# VDA_spanish.net
KiCad netlist of a schematic drawn in EAGLE
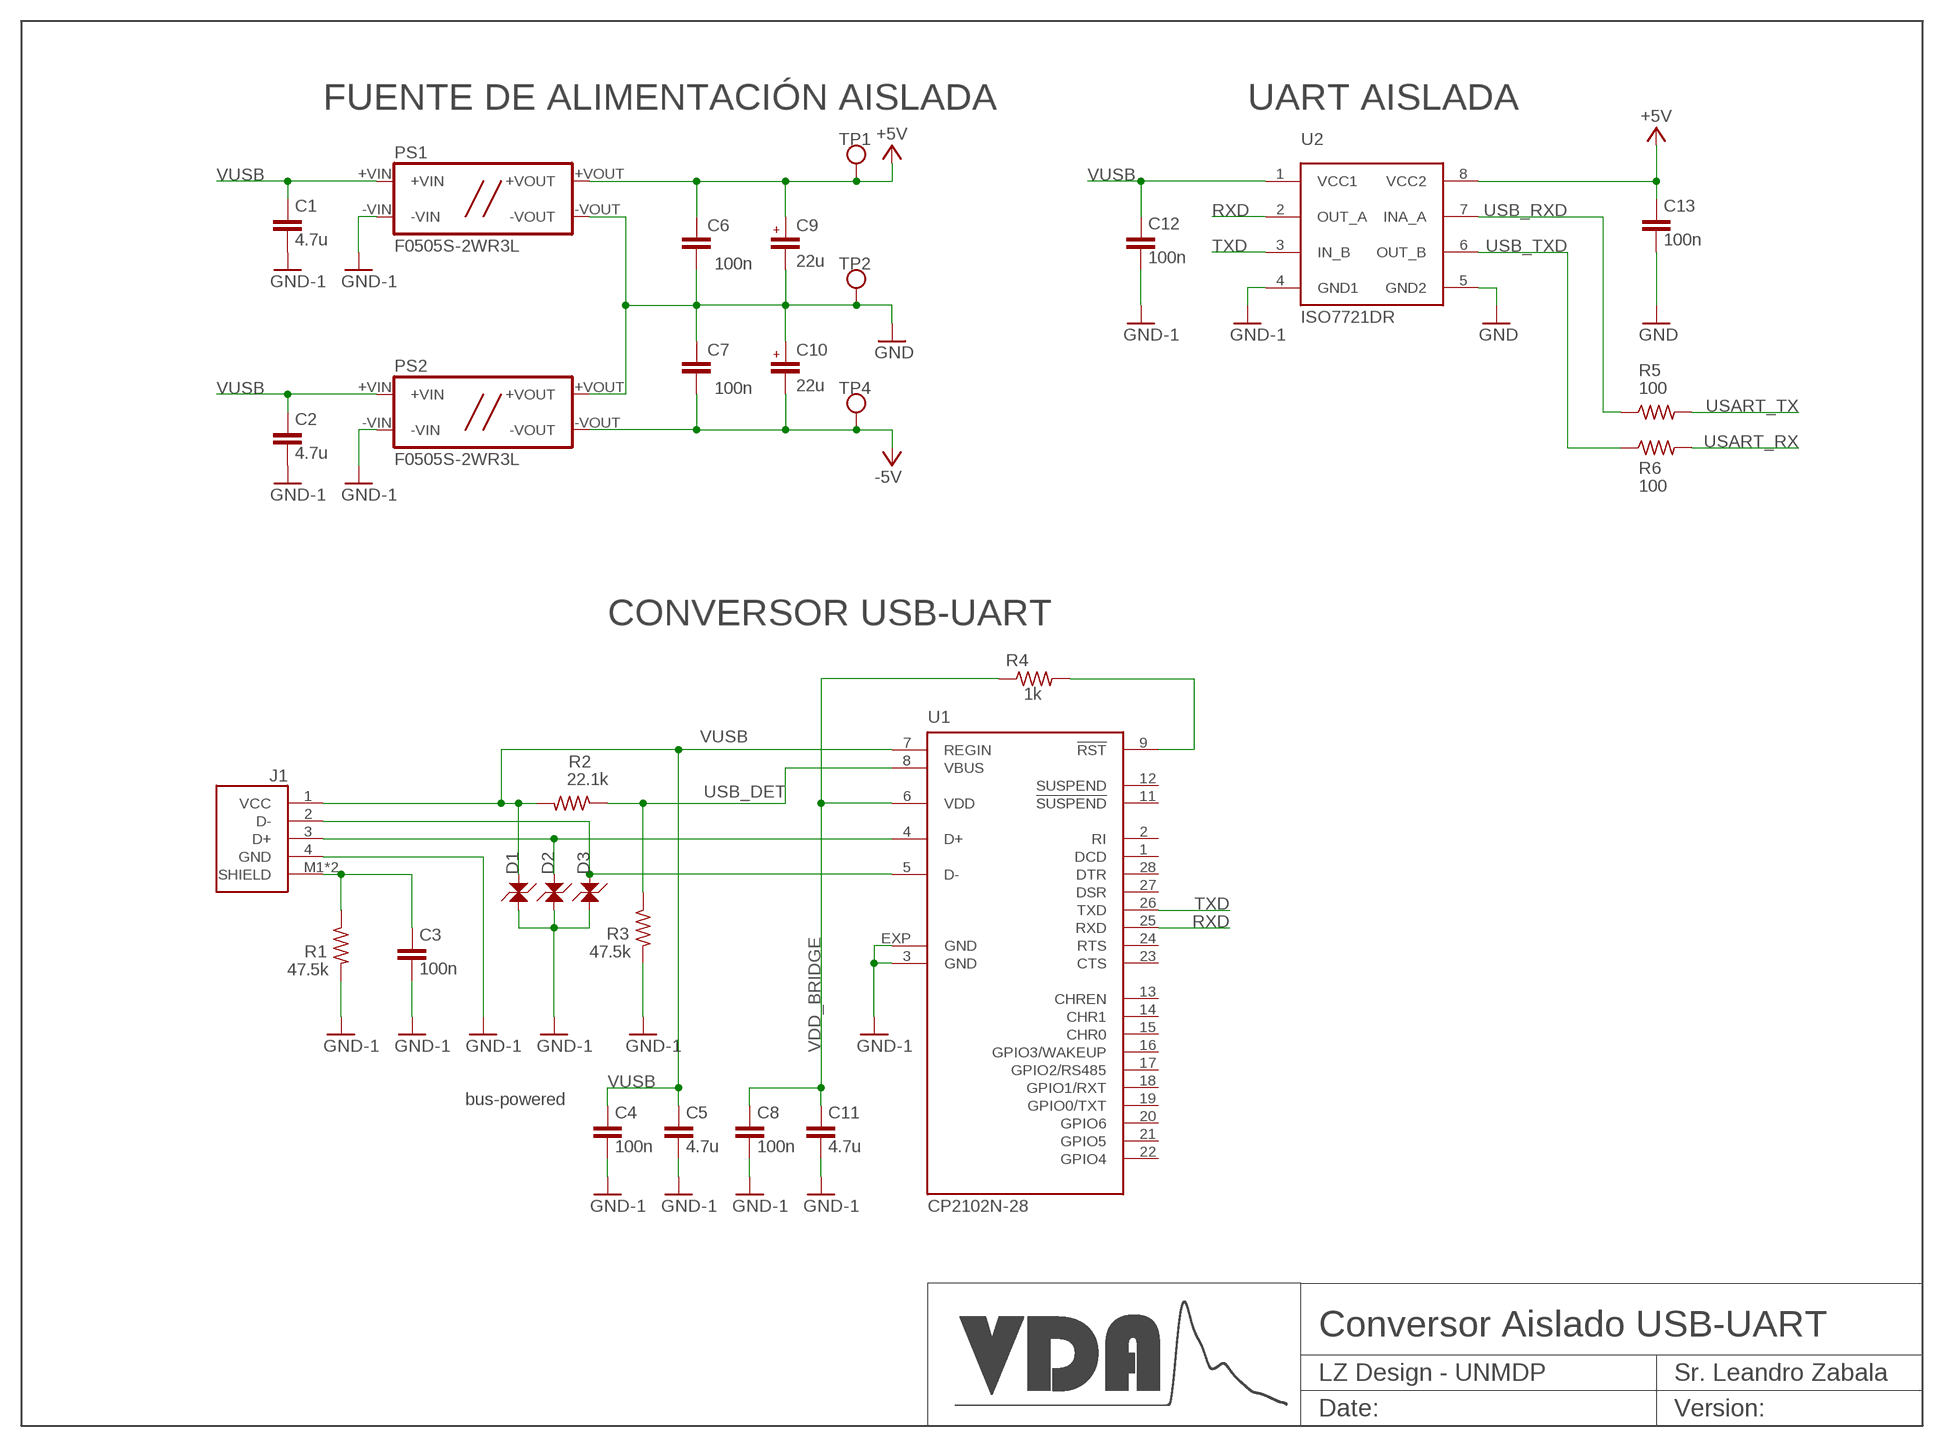
[diagram p0: schematic, sheet 1]
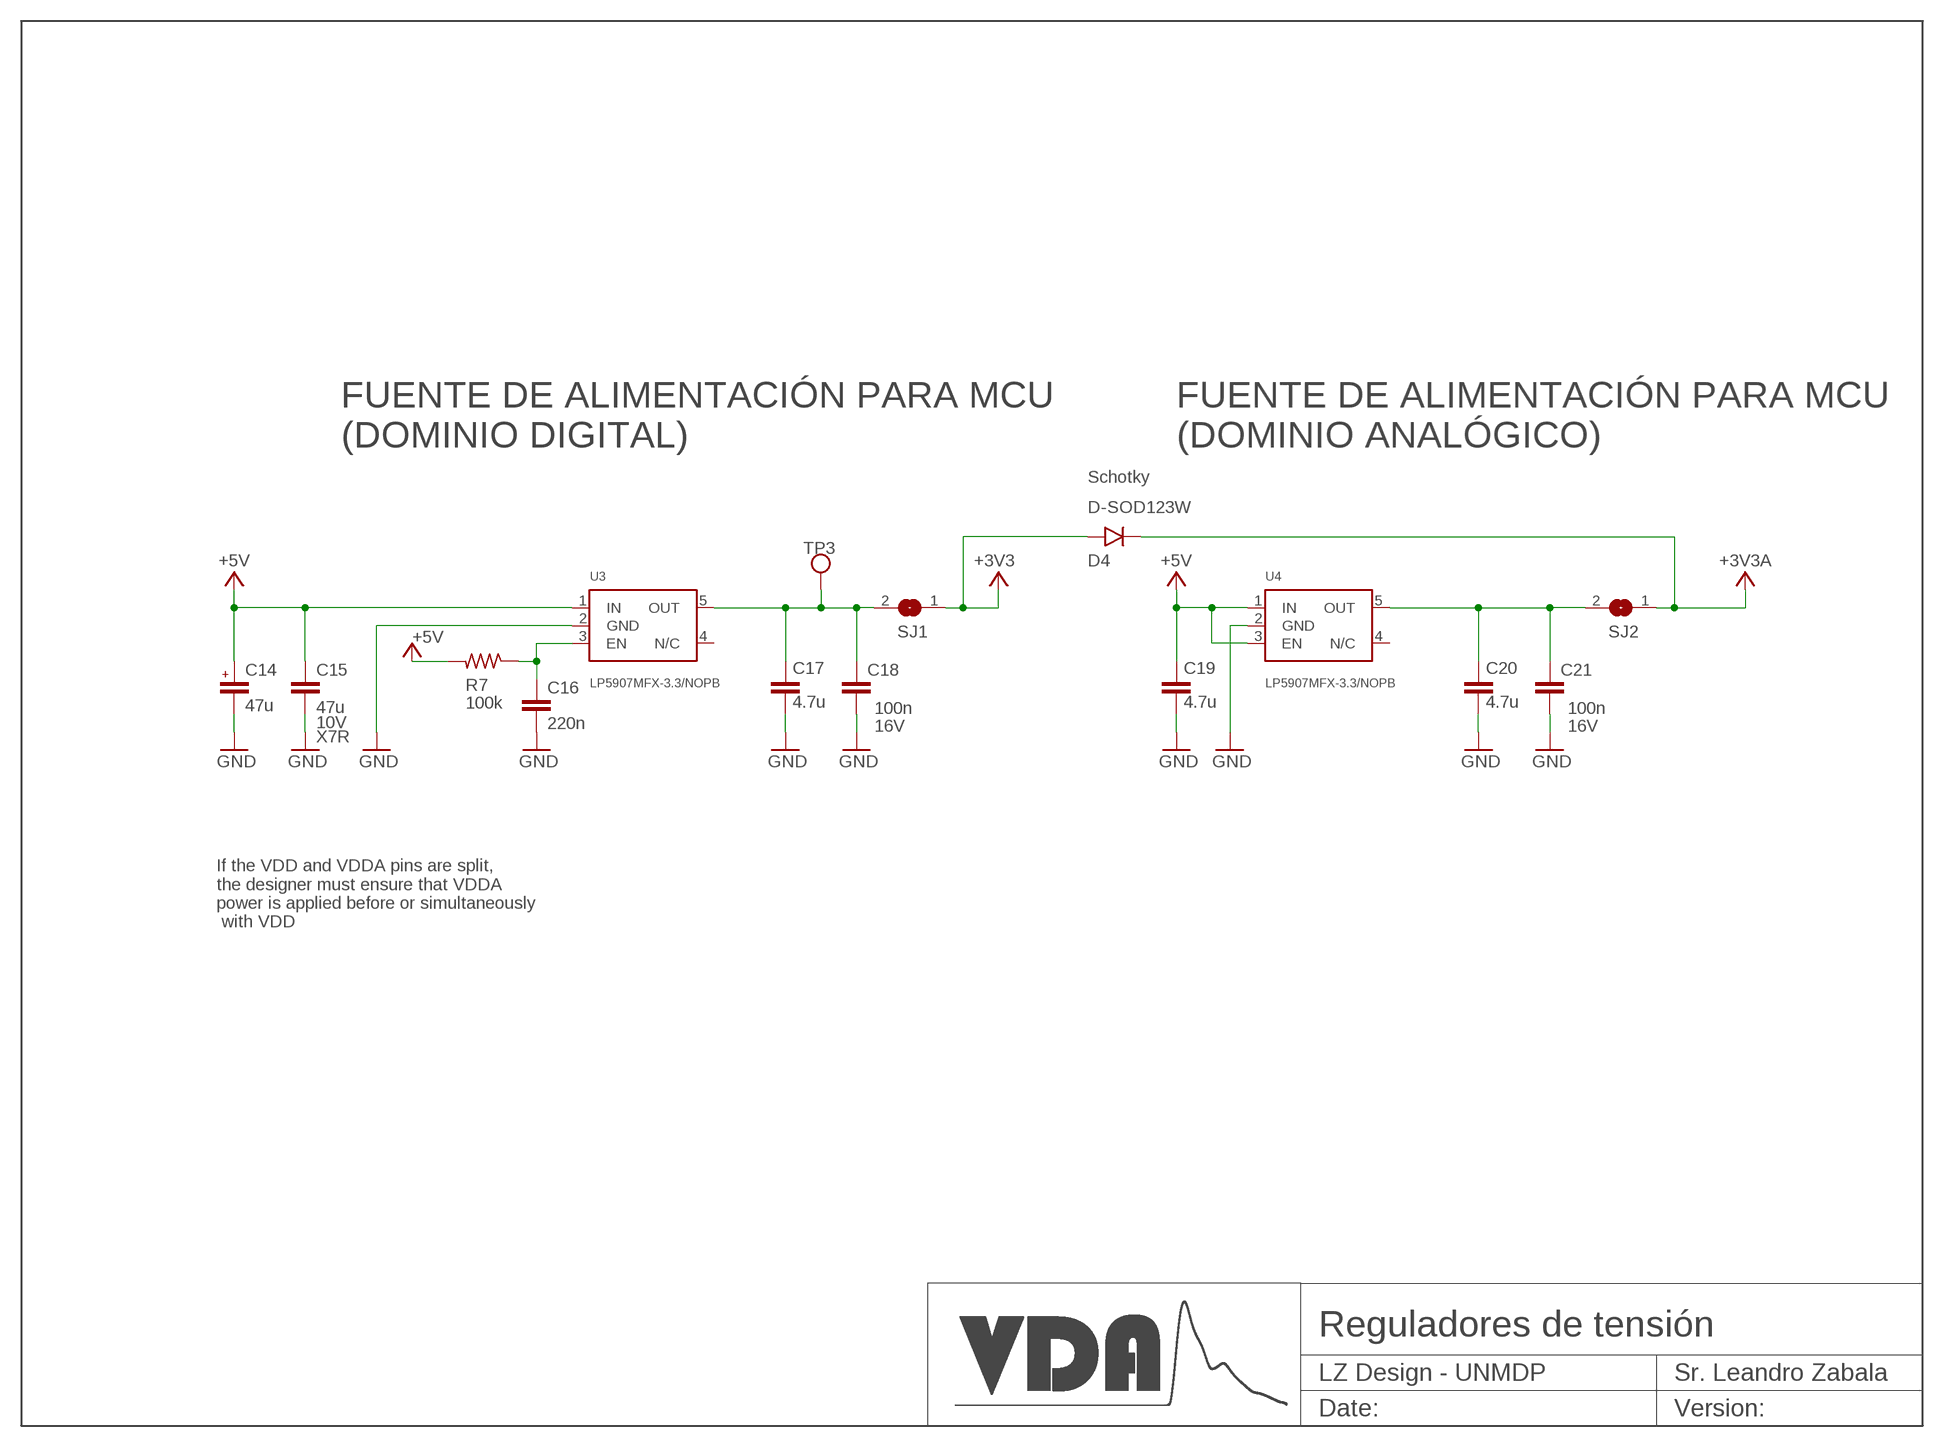
[diagram p1: schematic, sheet 2]
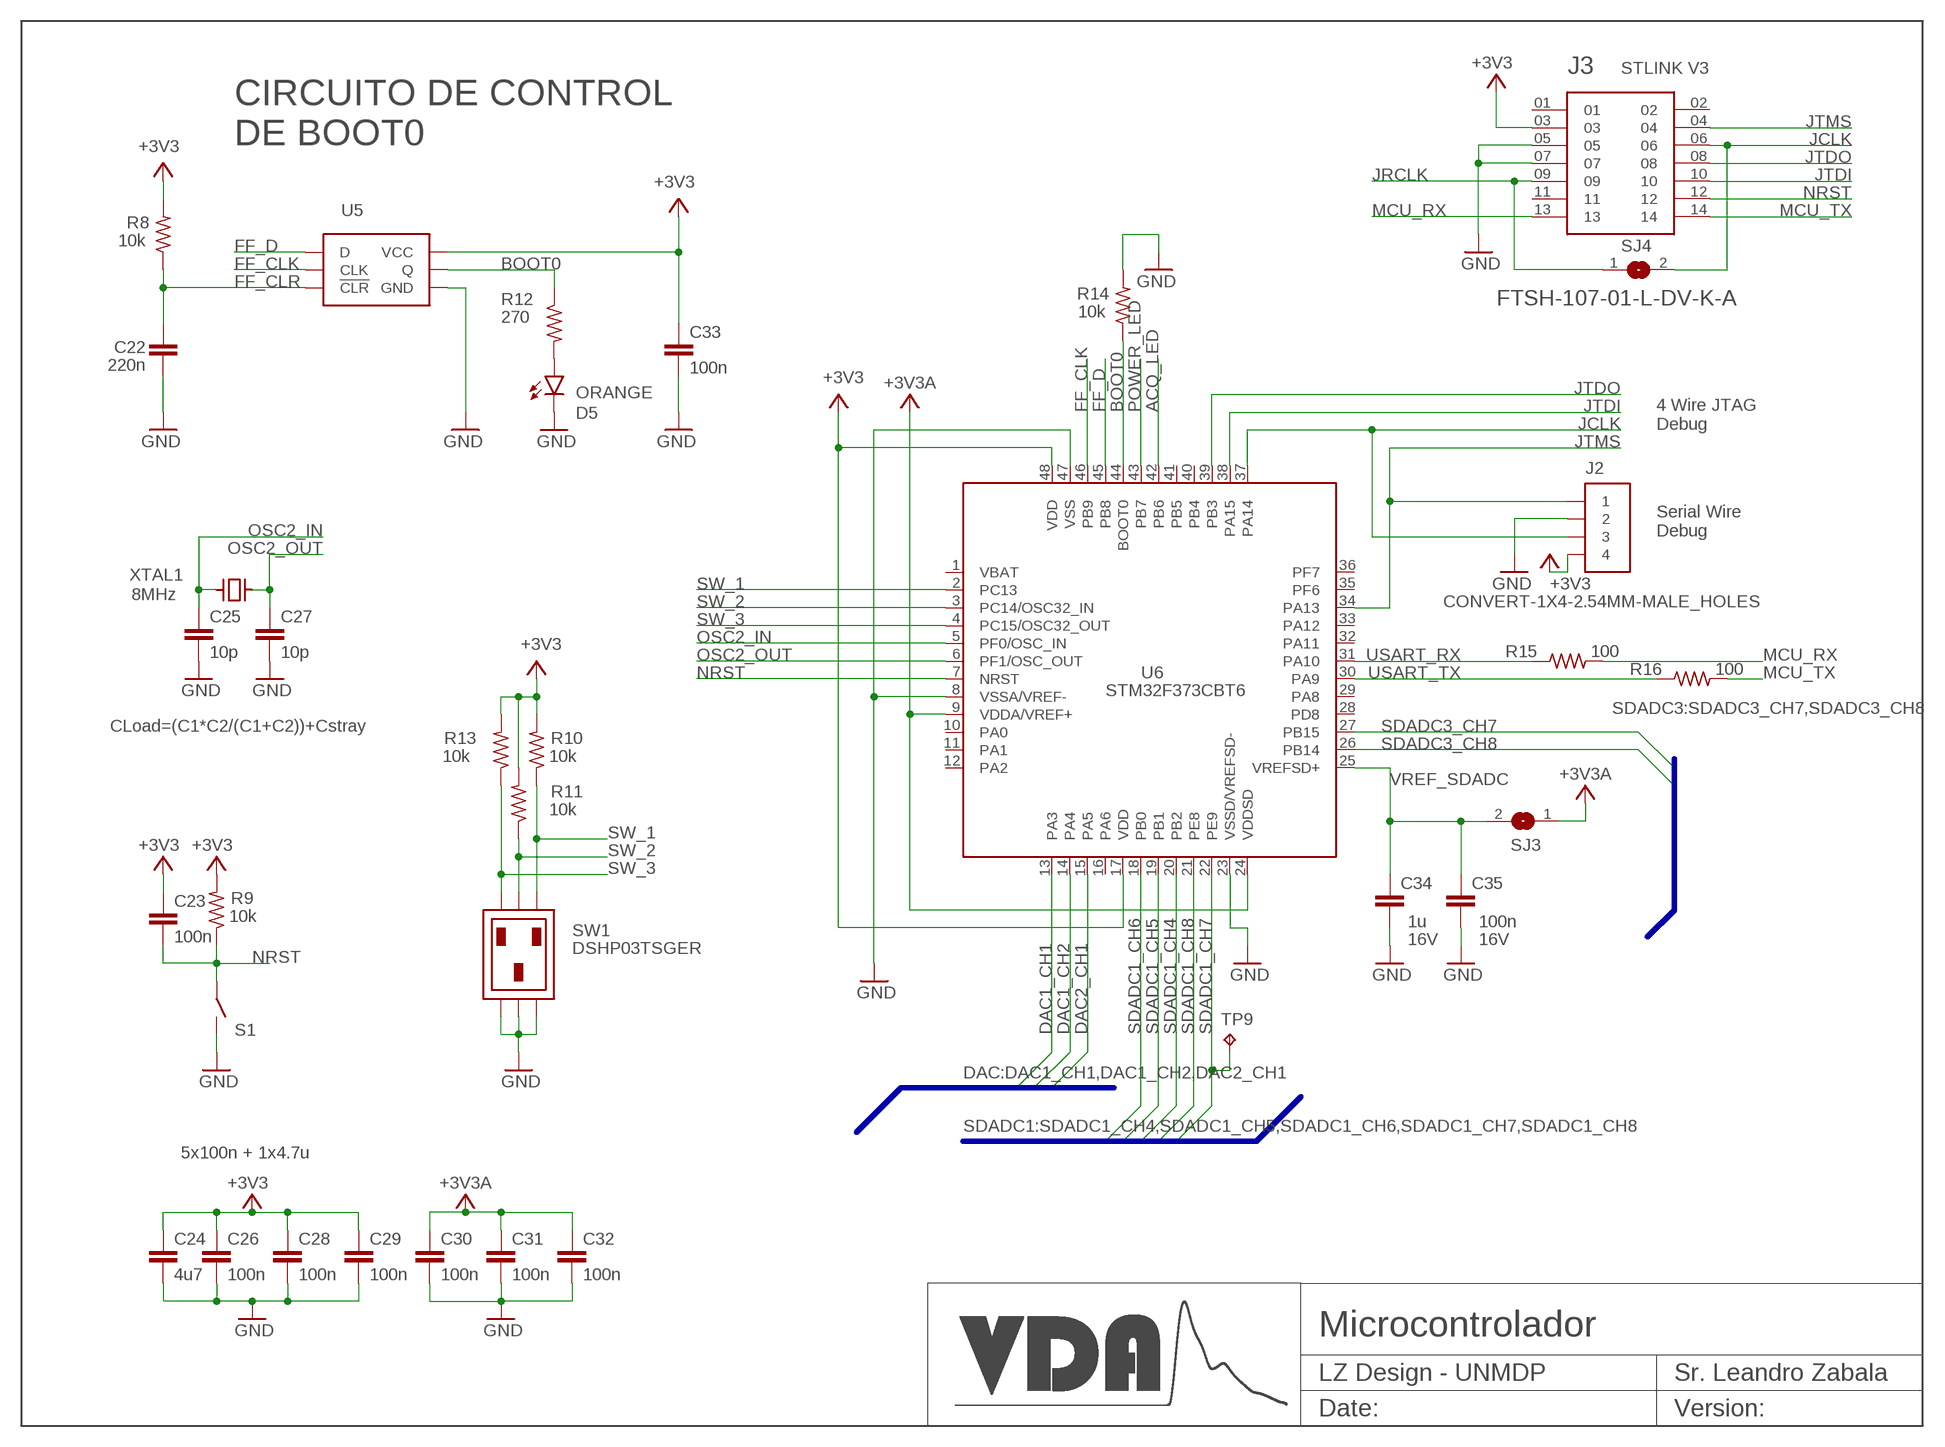
[diagram p2: schematic, sheet 3]
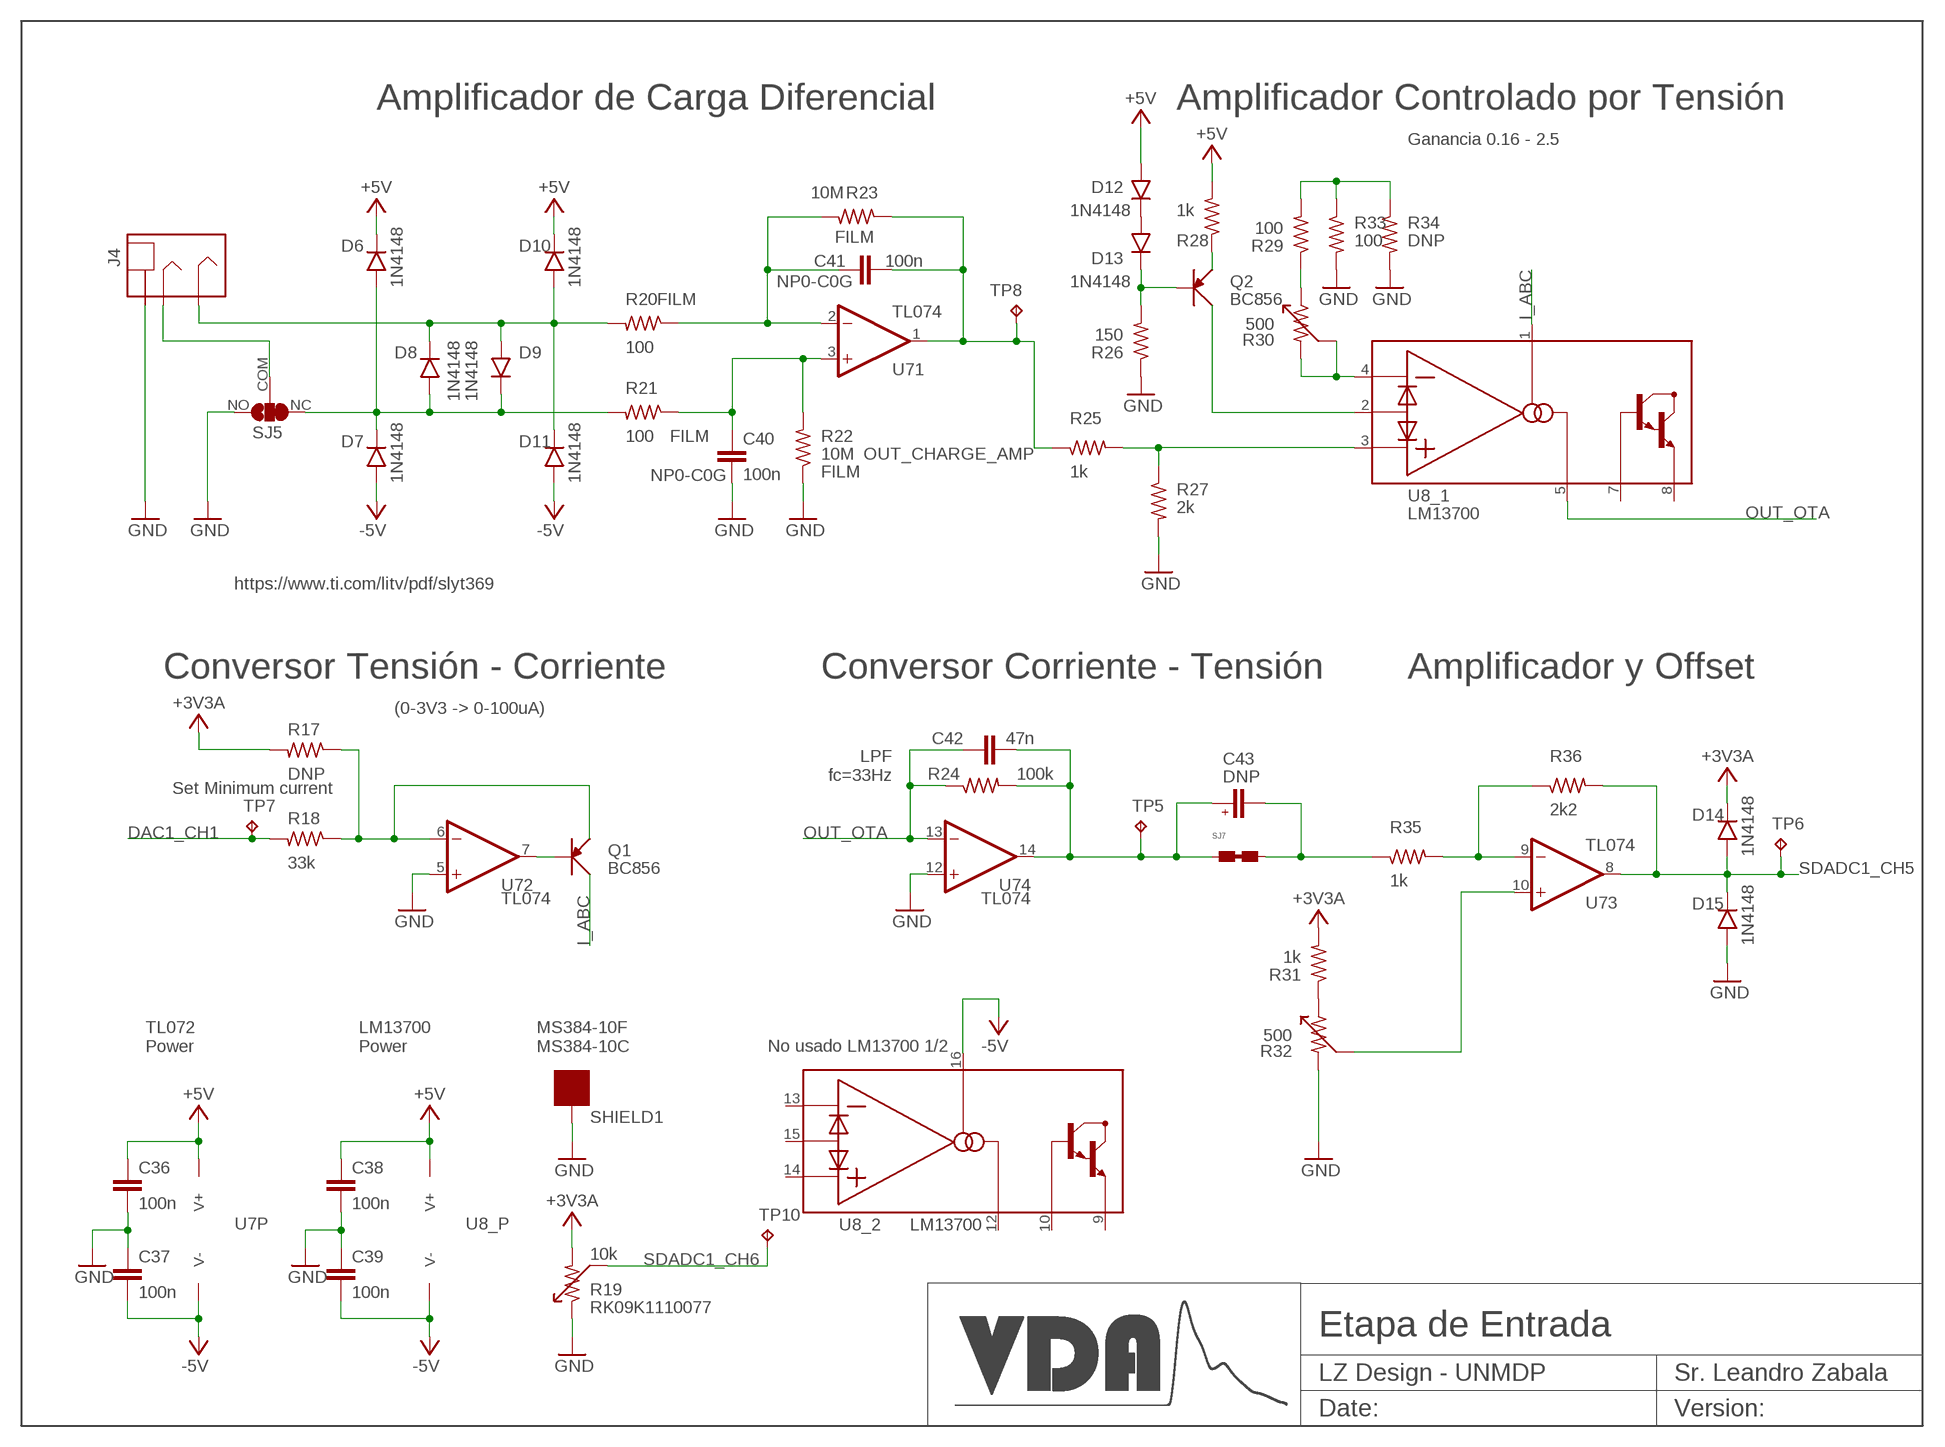
[diagram p3: schematic, sheet 4]
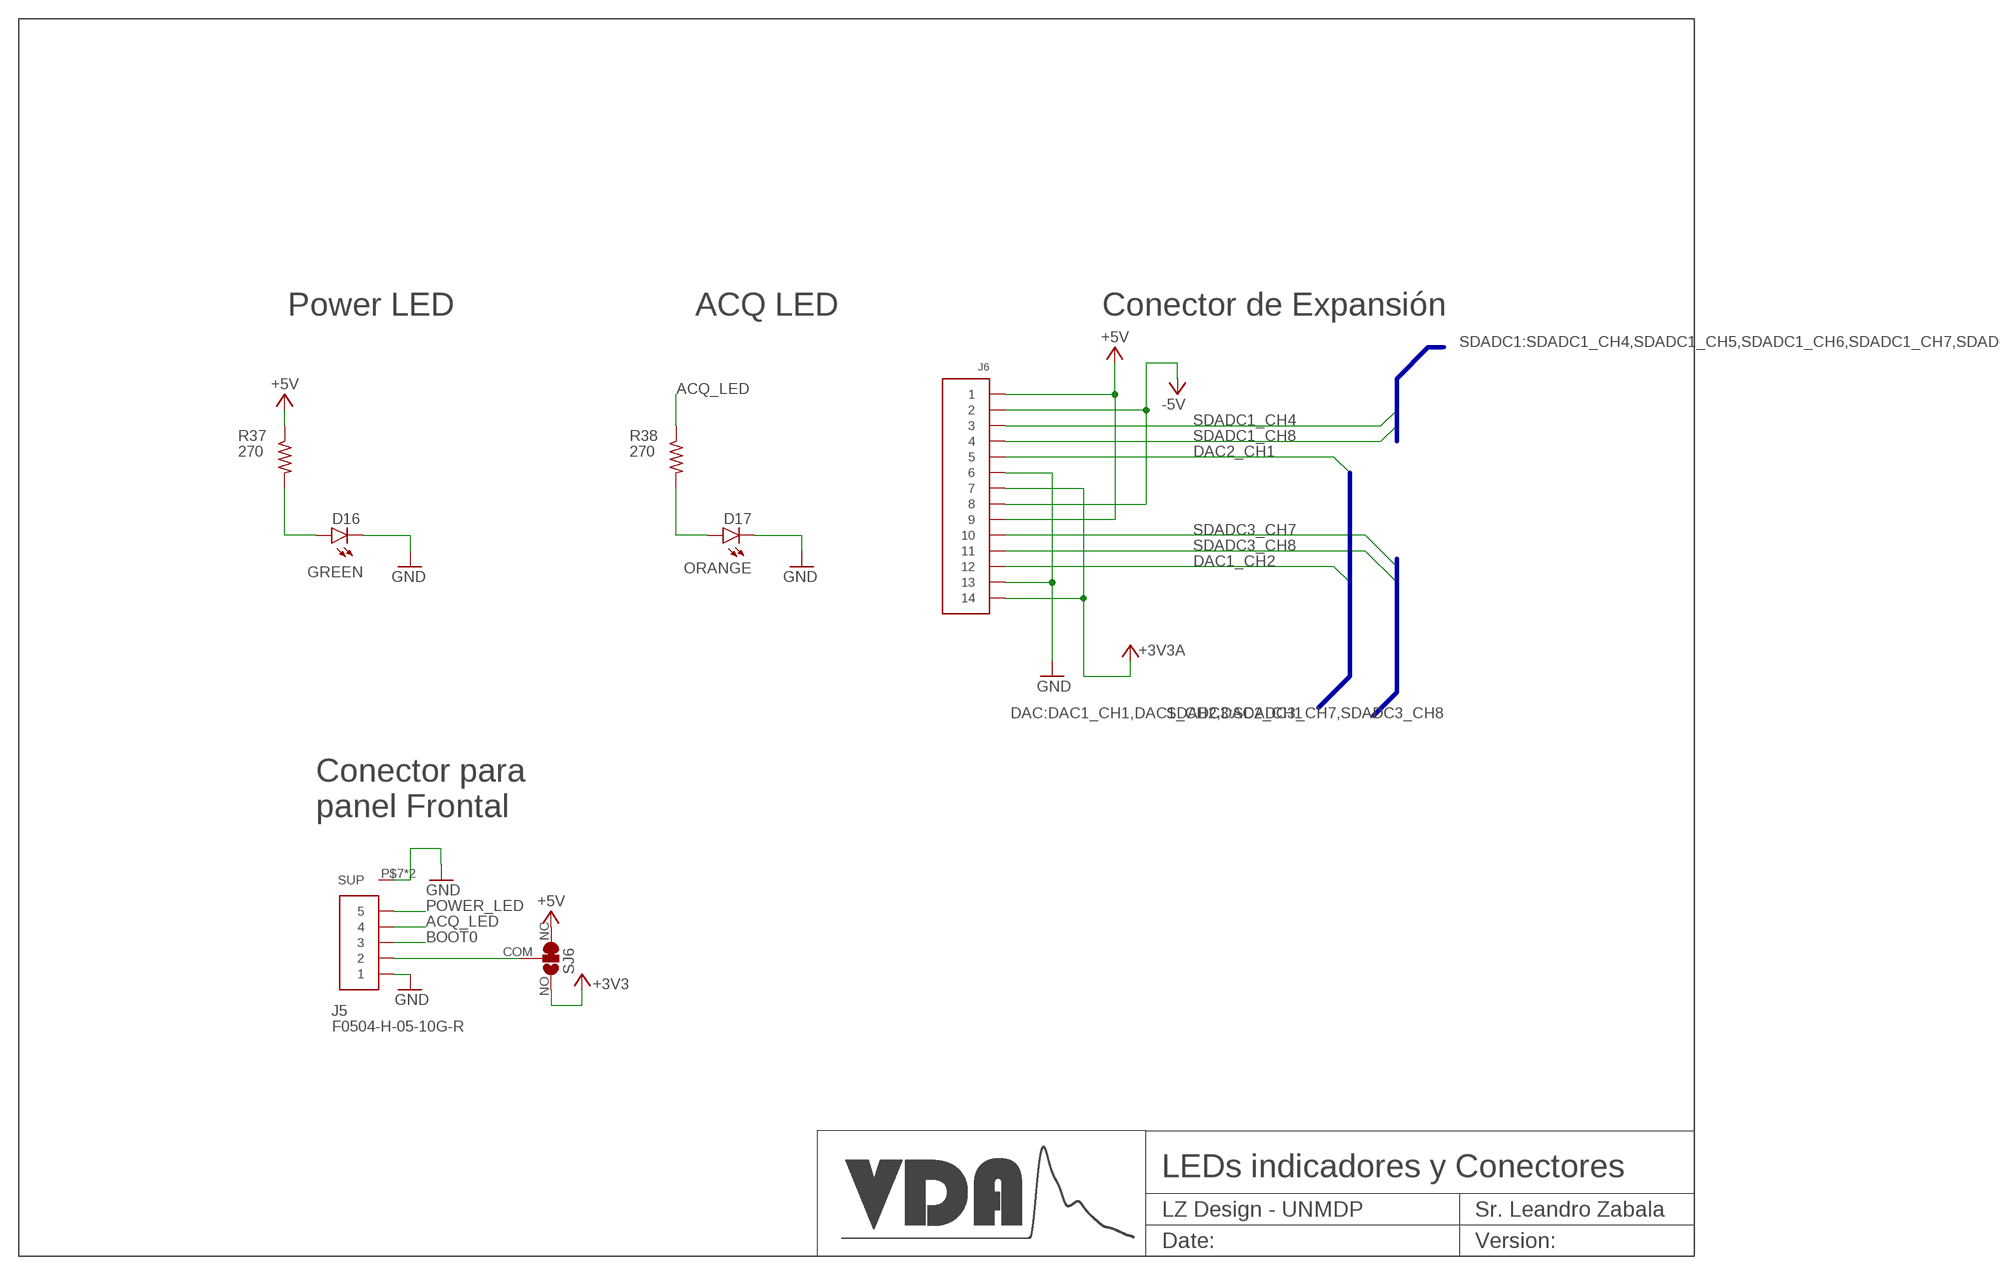
[diagram p4: schematic, sheet 5]

(export (version "E")
  (design (tool "Eeschema 10.0.6"))
  (components
    (comp (ref "C1")
      (value "4.7u")
      (footprint "eagle-import:C_0805")
      (libsource (lib "eagle-import") (part "C_0805"))
    )
    (comp (ref "C2")
      (value "4.7u")
      (footprint "eagle-import:C_0805")
      (libsource (lib "eagle-import") (part "C_0805"))
    )
    (comp (ref "C3")
      (value "100n")
      (footprint "eagle-import:C_0603")
      (libsource (lib "eagle-import") (part "C_0603"))
    )
    (comp (ref "C4")
      (value "100n")
      (footprint "eagle-import:C_0603")
      (libsource (lib "eagle-import") (part "C_0603"))
    )
    (comp (ref "C5")
      (value "4.7u")
      (footprint "eagle-import:C_0805")
      (libsource (lib "eagle-import") (part "C_0805"))
    )
    (comp (ref "C6")
      (value "100n")
      (footprint "eagle-import:C_0603")
      (libsource (lib "eagle-import") (part "C_0603"))
    )
    (comp (ref "C7")
      (value "100n")
      (footprint "eagle-import:C_0603")
      (libsource (lib "eagle-import") (part "C_0603"))
    )
    (comp (ref "C8")
      (value "100n")
      (footprint "eagle-import:C_0603")
      (libsource (lib "eagle-import") (part "C_0603"))
    )
    (comp (ref "C9")
      (value "22u")
      (footprint "eagle-import:CAPAE660X590N")
      (libsource (lib "eagle-import") (part "C-ELECT-6.3X5.4"))
    )
    (comp (ref "C10")
      (value "22u")
      (footprint "eagle-import:CAPAE660X590N")
      (libsource (lib "eagle-import") (part "C-ELECT-6.3X5.4"))
    )
    (comp (ref "C11")
      (value "4.7u")
      (footprint "eagle-import:C_0805")
      (libsource (lib "eagle-import") (part "C_0805"))
    )
    (comp (ref "C12")
      (value "100n")
      (footprint "eagle-import:C_0603")
      (libsource (lib "eagle-import") (part "C_0603"))
    )
    (comp (ref "C13")
      (value "100n")
      (footprint "eagle-import:C_0603")
      (libsource (lib "eagle-import") (part "C_0603"))
    )
    (comp (ref "D1")
      (value "LESD5D5.0CT1G")
      (footprint "eagle-import:SOD523")
      (libsource (lib "eagle-import") (part "LESD5D5.0CT1G"))
    )
    (comp (ref "D2")
      (value "LESD5D5.0CT1G")
      (footprint "eagle-import:SOD523")
      (libsource (lib "eagle-import") (part "LESD5D5.0CT1G"))
    )
    (comp (ref "D3")
      (value "LESD5D5.0CT1G")
      (footprint "eagle-import:SOD523")
      (libsource (lib "eagle-import") (part "LESD5D5.0CT1G"))
    )
    (comp (ref "J1")
      (value "USB-2.0")
      (footprint "eagle-import:USB-B")
      (libsource (lib "eagle-import") (part "USB-2.0"))
    )
    (comp (ref "PS1")
      (value "F0505S-2WR3L")
      (footprint "eagle-import:0505S-2WR3")
      (libsource (lib "eagle-import") (part "ISOLATED_DCDC"))
    )
    (comp (ref "PS2")
      (value "F0505S-2WR3L")
      (footprint "eagle-import:0505S-2WR3")
      (libsource (lib "eagle-import") (part "ISOLATED_DCDC"))
    )
    (comp (ref "R1")
      (value "47.5k")
      (footprint "eagle-import:R0402")
      (libsource (lib "eagle-import") (part "R-US_R0402"))
    )
    (comp (ref "R2")
      (value "22.1k")
      (footprint "eagle-import:R0402")
      (libsource (lib "eagle-import") (part "R-US_R0402"))
    )
    (comp (ref "R3")
      (value "47.5k")
      (footprint "eagle-import:R0402")
      (libsource (lib "eagle-import") (part "R-US_R0402"))
    )
    (comp (ref "R4")
      (value "1k")
      (footprint "eagle-import:R0402")
      (libsource (lib "eagle-import") (part "R-US_R0402"))
    )
    (comp (ref "R5")
      (value "100")
      (footprint "eagle-import:R_0603")
      (libsource (lib "eagle-import") (part "R_0603"))
    )
    (comp (ref "R6")
      (value "100")
      (footprint "eagle-import:R_0603")
      (libsource (lib "eagle-import") (part "R_0603"))
    )
    (comp (ref "TP1")
      (value "HOLE_0.8MM")
      (footprint "eagle-import:HOLE_0.8MM")
      (libsource (lib "eagle-import") (part "HOLE_0.8MM"))
    )
    (comp (ref "TP2")
      (value "HOLE_0.8MM")
      (footprint "eagle-import:HOLE_0.8MM")
      (libsource (lib "eagle-import") (part "HOLE_0.8MM"))
    )
    (comp (ref "TP4")
      (value "HOLE_0.8MM")
      (footprint "eagle-import:HOLE_0.8MM")
      (libsource (lib "eagle-import") (part "HOLE_0.8MM"))
    )
    (comp (ref "U1")
      (value "CP2102N-28")
      (footprint "eagle-import:MLP28")
      (libsource (lib "eagle-import") (part "CP2102N-28"))
    )
    (comp (ref "U2")
      (value "ISO7721DR")
      (footprint "eagle-import:SO8")
      (libsource (lib "eagle-import") (part "ISO7721DR"))
    )
    (comp (ref "C22")
      (value "220n")
      (footprint "eagle-import:C_0603")
      (libsource (lib "eagle-import") (part "C_0603"))
    )
    (comp (ref "C23")
      (value "100n")
      (footprint "eagle-import:C_0603")
      (libsource (lib "eagle-import") (part "C_0603"))
    )
    (comp (ref "C24")
      (value "4u7")
      (footprint "eagle-import:C_0805")
      (libsource (lib "eagle-import") (part "C_0805"))
    )
    (comp (ref "C25")
      (value "10p")
      (footprint "eagle-import:C_0603")
      (libsource (lib "eagle-import") (part "C_0603"))
    )
    (comp (ref "C26")
      (value "100n")
      (footprint "eagle-import:C_0603")
      (libsource (lib "eagle-import") (part "C_0603"))
    )
    (comp (ref "C27")
      (value "10p")
      (footprint "eagle-import:C_0603")
      (libsource (lib "eagle-import") (part "C_0603"))
    )
    (comp (ref "C28")
      (value "100n")
      (footprint "eagle-import:C_0603")
      (libsource (lib "eagle-import") (part "C_0603"))
    )
    (comp (ref "C29")
      (value "100n")
      (footprint "eagle-import:C_0603")
      (libsource (lib "eagle-import") (part "C_0603"))
    )
    (comp (ref "C30")
      (value "100n")
      (footprint "eagle-import:C_0603")
      (libsource (lib "eagle-import") (part "C_0603"))
    )
    (comp (ref "C31")
      (value "100n")
      (footprint "eagle-import:C_0603")
      (libsource (lib "eagle-import") (part "C_0603"))
    )
    (comp (ref "C32")
      (value "100n")
      (footprint "eagle-import:C_0603")
      (libsource (lib "eagle-import") (part "C_0603"))
    )
    (comp (ref "C33")
      (value "100n")
      (footprint "eagle-import:C_0603")
      (libsource (lib "eagle-import") (part "C_0603"))
    )
    (comp (ref "C34")
      (value "1u")
      (footprint "eagle-import:C_0603")
      (fields (field (name "V") "16V"))
      (libsource (lib "eagle-import") (part "C_0603"))
    )
    (comp (ref "C35")
      (value "100n")
      (footprint "eagle-import:C_0603")
      (fields (field (name "V") "16V"))
      (libsource (lib "eagle-import") (part "C_0603"))
    )
    (comp (ref "D5")
      (value "ORANGE")
      (footprint "eagle-import:LED_0603_ARROW")
      (libsource (lib "eagle-import") (part "LED_0603_ARROW"))
    )
    (comp (ref "J2")
      (value "CONVERT-1X4-2.54MM-MALE_HOLES")
      (footprint "eagle-import:1X04")
      (libsource (lib "eagle-import") (part "CONVERT-1X4-2.54MM-MALE_HOLES"))
    )
    (comp (ref "J3")
      (value "FTSH-107-01-L-DV-K-A")
      (footprint "eagle-import:SAMTEC_FTSH-107-01-L-DV-K-A")
      (fields (field (name "MANUFACTURER") "Samtec"))
      (libsource (lib "eagle-import") (part "FTSH-107-01-L-DV-K-A"))
    )
    (comp (ref "R8")
      (value "10k")
      (footprint "eagle-import:R_0603")
      (libsource (lib "eagle-import") (part "R_0603"))
    )
    (comp (ref "R9")
      (value "10k")
      (footprint "eagle-import:R_0603")
      (libsource (lib "eagle-import") (part "R_0603"))
    )
    (comp (ref "R10")
      (value "10k")
      (footprint "eagle-import:R_0603")
      (libsource (lib "eagle-import") (part "R_0603"))
    )
    (comp (ref "R11")
      (value "10k")
      (footprint "eagle-import:R_0603")
      (libsource (lib "eagle-import") (part "R_0603"))
    )
    (comp (ref "R12")
      (value "270")
      (footprint "eagle-import:R_0603")
      (libsource (lib "eagle-import") (part "R_0603"))
    )
    (comp (ref "R13")
      (value "10k")
      (footprint "eagle-import:R_0603")
      (libsource (lib "eagle-import") (part "R_0603"))
    )
    (comp (ref "R14")
      (value "10k")
      (footprint "eagle-import:R_0603")
      (libsource (lib "eagle-import") (part "R_0603"))
    )
    (comp (ref "R15")
      (value "100")
      (footprint "eagle-import:R_0603")
      (libsource (lib "eagle-import") (part "R_0603"))
    )
    (comp (ref "R16")
      (value "100")
      (footprint "eagle-import:R_0603")
      (libsource (lib "eagle-import") (part "R_0603"))
    )
    (comp (ref "S1")
      (value "TSWITCH_SMTR2")
      (footprint "eagle-import:SMTR2")
      (libsource (lib "eagle-import") (part "TSWITCH_SMTR2"))
    )
    (comp (ref "SJ3") (value "SJ") (footprint "eagle-import:SJ") (libsource (lib "eagle-import") (part "SJ")))
    (comp (ref "SJ4") (value "SJ") (footprint "eagle-import:SJ") (libsource (lib "eagle-import") (part "SJ")))
    (comp (ref "SW1")
      (value "DSHP03TSGER")
      (footprint "eagle-import:DIPSW-3")
      (libsource (lib "eagle-import") (part "DIPSW-3"))
    )
    (comp (ref "TP9")
      (value "TPTP16R")
      (footprint "eagle-import:TP16R")
      (libsource (lib "eagle-import") (part "TPTP16R"))
    )
    (comp (ref "U5")
      (value "SN74LVC1G175")
      (footprint "eagle-import:SOT-23-6")
      (libsource (lib "eagle-import") (part "SN74LVC1G175"))
    )
    (comp (ref "U6")
      (value "STM32F373CBT6")
      (footprint "eagle-import:QFP50P900X900X160-48N")
      (libsource (lib "eagle-import") (part "STM32F373-48CT"))
    )
    (comp (ref "XTAL1")
      (value "8MHz")
      (footprint "eagle-import:XTAL3.2X2.5")
      (fields (field (name "MPN") "830108313809"))
      (libsource (lib "eagle-import") (part "XTAL3.2X2.5"))
    )
    (comp (ref "D16")
      (value "GREEN")
      (footprint "eagle-import:LED_0603_ARROW")
      (libsource (lib "eagle-import") (part "LED_0603_ARROW"))
    )
    (comp (ref "D17")
      (value "ORANGE")
      (footprint "eagle-import:LED_0603_ARROW")
      (libsource (lib "eagle-import") (part "LED_0603_ARROW"))
    )
    (comp (ref "J5")
      (value "F0504-H-05-10G-R")
      (footprint "eagle-import:F0504-H-05-10G-R")
      (libsource (lib "eagle-import") (part "F0504-H-05-10G-R"))
    )
    (comp (ref "J6")
      (value "CONVERT-2X7-2.54MM-FEMALE")
      (footprint "eagle-import:CONN-VERT-2.54MM-2X7-FEMALE")
      (libsource (lib "eagle-import") (part "CONVERT-2X7-2.54MM-FEMALE"))
    )
    (comp (ref "R37")
      (value "270")
      (footprint "eagle-import:R_0603")
      (libsource (lib "eagle-import") (part "R_0603"))
    )
    (comp (ref "R38")
      (value "270")
      (footprint "eagle-import:R_0603")
      (libsource (lib "eagle-import") (part "R_0603"))
    )
    (comp (ref "SJ6")
      (value "SJ-PSS")
      (footprint "eagle-import:SJ_2S")
      (libsource (lib "eagle-import") (part "SJ-PSS"))
    )
    (comp (ref "C14")
      (value "47u")
      (footprint "eagle-import:A_3216")
      (libsource (lib "eagle-import") (part "C-TANTALUM_A_3216"))
    )
    (comp (ref "C15")
      (value "47u")
      (footprint "eagle-import:C_1206")
      (fields (field (name "D") "X7R") (field (name "ESR") "LOW") (field (name "V") "10V"))
      (libsource (lib "eagle-import") (part "C_1206"))
    )
    (comp (ref "C16")
      (value "220n")
      (footprint "eagle-import:C_0603")
      (libsource (lib "eagle-import") (part "C_0603"))
    )
    (comp (ref "C17")
      (value "4.7u")
      (footprint "eagle-import:C_0805")
      (libsource (lib "eagle-import") (part "C_0805"))
    )
    (comp (ref "C18")
      (value "100n")
      (footprint "eagle-import:C_0603")
      (fields (field (name "V") "16V"))
      (libsource (lib "eagle-import") (part "C_0603"))
    )
    (comp (ref "C19")
      (value "4.7u")
      (footprint "eagle-import:C_0805")
      (libsource (lib "eagle-import") (part "C_0805"))
    )
    (comp (ref "C20")
      (value "4.7u")
      (footprint "eagle-import:C_0805")
      (libsource (lib "eagle-import") (part "C_0805"))
    )
    (comp (ref "C21")
      (value "100n")
      (footprint "eagle-import:C_0603")
      (fields (field (name "V") "16V"))
      (libsource (lib "eagle-import") (part "C_0603"))
    )
    (comp (ref "D4")
      (value "D-SOD123W")
      (footprint "eagle-import:SOD123W")
      (fields (field (name "TYPE") "Schotky"))
      (libsource (lib "eagle-import") (part "D-SOD123W"))
    )
    (comp (ref "R7")
      (value "100k")
      (footprint "eagle-import:R_0603")
      (libsource (lib "eagle-import") (part "R_0603"))
    )
    (comp (ref "SJ1") (value "SJ") (footprint "eagle-import:SJ") (libsource (lib "eagle-import") (part "SJ")))
    (comp (ref "SJ2") (value "SJ") (footprint "eagle-import:SJ") (libsource (lib "eagle-import") (part "SJ")))
    (comp (ref "TP3")
      (value "HOLE_0.8MM")
      (footprint "eagle-import:HOLE_0.8MM")
      (libsource (lib "eagle-import") (part "HOLE_0.8MM"))
    )
    (comp (ref "U3")
      (value "LP5907MFX-3.3/NOPB")
      (footprint "eagle-import:SOT23-5")
      (libsource (lib "eagle-import") (part "LDO1SOT23-5_1"))
    )
    (comp (ref "U4")
      (value "LP5907MFX-3.3/NOPB")
      (footprint "eagle-import:SOT23-5")
      (libsource (lib "eagle-import") (part "LDO1SOT23-5_1"))
    )
    (comp (ref "C36")
      (value "100n")
      (footprint "eagle-import:C_0603")
      (libsource (lib "eagle-import") (part "C_0603"))
    )
    (comp (ref "C37")
      (value "100n")
      (footprint "eagle-import:C_0603")
      (libsource (lib "eagle-import") (part "C_0603"))
    )
    (comp (ref "C38")
      (value "100n")
      (footprint "eagle-import:C_0603")
      (libsource (lib "eagle-import") (part "C_0603"))
    )
    (comp (ref "C39")
      (value "100n")
      (footprint "eagle-import:C_0603")
      (libsource (lib "eagle-import") (part "C_0603"))
    )
    (comp (ref "C40")
      (value "100n")
      (footprint "eagle-import:C_1206")
      (description "NP0-C0G")
      (libsource (lib "eagle-import") (part "C_1206"))
    )
    (comp (ref "C41")
      (value "100n")
      (footprint "eagle-import:C_1206")
      (description "NP0-C0G")
      (libsource (lib "eagle-import") (part "C_1206"))
    )
    (comp (ref "C42")
      (value "47n")
      (footprint "eagle-import:C_0603")
      (libsource (lib "eagle-import") (part "C_0603"))
    )
    (comp (ref "C43")
      (value "DNP")
      (footprint "eagle-import:CAPAE830X680N")
      (libsource (lib "eagle-import") (part "C-ELECT_D8L6.5"))
    )
    (comp (ref "D6")
      (value "1N4148")
      (footprint "eagle-import:SOD123W")
      (libsource (lib "eagle-import") (part "D-SOD123W"))
    )
    (comp (ref "D7")
      (value "1N4148")
      (footprint "eagle-import:SOD123W")
      (libsource (lib "eagle-import") (part "D-SOD123W"))
    )
    (comp (ref "D8")
      (value "1N4148")
      (footprint "eagle-import:SOD123W")
      (libsource (lib "eagle-import") (part "D-SOD123W"))
    )
    (comp (ref "D9")
      (value "1N4148")
      (footprint "eagle-import:SOD123W")
      (libsource (lib "eagle-import") (part "D-SOD123W"))
    )
    (comp (ref "D10")
      (value "1N4148")
      (footprint "eagle-import:SOD123W")
      (libsource (lib "eagle-import") (part "D-SOD123W"))
    )
    (comp (ref "D11")
      (value "1N4148")
      (footprint "eagle-import:SOD123W")
      (libsource (lib "eagle-import") (part "D-SOD123W"))
    )
    (comp (ref "D12")
      (value "1N4148")
      (footprint "eagle-import:SOD123W")
      (libsource (lib "eagle-import") (part "D-SOD123W"))
    )
    (comp (ref "D13")
      (value "1N4148")
      (footprint "eagle-import:SOD123W")
      (libsource (lib "eagle-import") (part "D-SOD123W"))
    )
    (comp (ref "D14")
      (value "1N4148")
      (footprint "eagle-import:SOD123W")
      (libsource (lib "eagle-import") (part "D-SOD123W"))
    )
    (comp (ref "D15")
      (value "1N4148")
      (footprint "eagle-import:SOD123W")
      (libsource (lib "eagle-import") (part "D-SOD123W"))
    )
    (comp (ref "J4")
      (value "STEREO-JACK")
      (footprint "eagle-import:PJ-3200")
      (libsource (lib "eagle-import") (part "STEREO-JACK"))
    )
    (comp (ref "Q1")
      (value "BC856")
      (footprint "eagle-import:SOT-23")
      (libsource (lib "eagle-import") (part "PNP_SOT23"))
    )
    (comp (ref "Q2")
      (value "BC856")
      (footprint "eagle-import:SOT-23")
      (libsource (lib "eagle-import") (part "PNP_SOT23"))
    )
    (comp (ref "R17")
      (value "DNP")
      (footprint "eagle-import:R_0603")
      (libsource (lib "eagle-import") (part "R_0603"))
    )
    (comp (ref "R18")
      (value "33k")
      (footprint "eagle-import:R_0603")
      (libsource (lib "eagle-import") (part "R_0603"))
    )
    (comp (ref "R19")
      (value "10k")
      (footprint "eagle-import:POT-09VR1M")
      (fields (field (name "MPN") "RK09K1110077"))
      (libsource (lib "eagle-import") (part "R-VARIABLE09VR1B"))
    )
    (comp (ref "R20")
      (value "100")
      (footprint "eagle-import:R_0603")
      (description "FILM")
      (libsource (lib "eagle-import") (part "R_0603"))
    )
    (comp (ref "R21")
      (value "100")
      (footprint "eagle-import:R_0603")
      (description "FILM")
      (libsource (lib "eagle-import") (part "R_0603"))
    )
    (comp (ref "R22")
      (value "10M")
      (footprint "eagle-import:R_0603")
      (description "FILM")
      (libsource (lib "eagle-import") (part "R_0603"))
    )
    (comp (ref "R23")
      (value "10M")
      (footprint "eagle-import:R_0603")
      (description "FILM")
      (libsource (lib "eagle-import") (part "R_0603"))
    )
    (comp (ref "R24")
      (value "100k")
      (footprint "eagle-import:R_0603")
      (libsource (lib "eagle-import") (part "R_0603"))
    )
    (comp (ref "R25")
      (value "1k")
      (footprint "eagle-import:R_0603")
      (libsource (lib "eagle-import") (part "R_0603"))
    )
    (comp (ref "R26")
      (value "150")
      (footprint "eagle-import:R_0603")
      (libsource (lib "eagle-import") (part "R_0603"))
    )
    (comp (ref "R27")
      (value "2k")
      (footprint "eagle-import:R_0603")
      (libsource (lib "eagle-import") (part "R_0603"))
    )
    (comp (ref "R28")
      (value "1k")
      (footprint "eagle-import:R_0603")
      (libsource (lib "eagle-import") (part "R_0603"))
    )
    (comp (ref "R29")
      (value "100")
      (footprint "eagle-import:R_0603")
      (libsource (lib "eagle-import") (part "R_0603"))
    )
    (comp (ref "R30")
      (value "500")
      (footprint "eagle-import:RV3.2X4")
      (fields (field (name "MPN") "3224W-1-501E"))
      (libsource (lib "eagle-import") (part "R-VARIABLE-3.2X4"))
    )
    (comp (ref "R31")
      (value "1k")
      (footprint "eagle-import:R_0603")
      (libsource (lib "eagle-import") (part "R_0603"))
    )
    (comp (ref "R32")
      (value "500")
      (footprint "eagle-import:RV3.2X4")
      (fields (field (name "MPN") "3224W-1-501E"))
      (libsource (lib "eagle-import") (part "R-VARIABLE-3.2X4"))
    )
    (comp (ref "R33")
      (value "100")
      (footprint "eagle-import:R_0603")
      (libsource (lib "eagle-import") (part "R_0603"))
    )
    (comp (ref "R34")
      (value "DNP")
      (footprint "eagle-import:R_0603")
      (libsource (lib "eagle-import") (part "R_0603"))
    )
    (comp (ref "R35")
      (value "1k")
      (footprint "eagle-import:R_0603")
      (libsource (lib "eagle-import") (part "R_0603"))
    )
    (comp (ref "R36")
      (value "2k2")
      (footprint "eagle-import:R_0603")
      (libsource (lib "eagle-import") (part "R_0603"))
    )
    (comp (ref "SHIELD1")
      (value "MS384")
      (footprint "eagle-import:MS384")
      (libsource (lib "eagle-import") (part "MS384"))
    )
    (comp (ref "SJ5")
      (value "SJ-PSS")
      (footprint "eagle-import:SJ_2S")
      (libsource (lib "eagle-import") (part "SJ-PSS"))
    )
    (comp (ref "SJ7")
      (value "SJUMPER-NC")
      (footprint "eagle-import:SJ1")
      (libsource (lib "eagle-import") (part "SJUMPER-NC"))
    )
    (comp (ref "TP5")
      (value "TPTP16R")
      (footprint "eagle-import:TP16R")
      (libsource (lib "eagle-import") (part "TPTP16R"))
    )
    (comp (ref "TP6")
      (value "TPTP16R")
      (footprint "eagle-import:TP16R")
      (libsource (lib "eagle-import") (part "TPTP16R"))
    )
    (comp (ref "TP7")
      (value "TPTP16R")
      (footprint "eagle-import:TP16R")
      (libsource (lib "eagle-import") (part "TPTP16R"))
    )
    (comp (ref "TP8")
      (value "TPTP16R")
      (footprint "eagle-import:TP16R")
      (libsource (lib "eagle-import") (part "TPTP16R"))
    )
    (comp (ref "TP10")
      (value "TPTP16R")
      (footprint "eagle-import:TP16R")
      (libsource (lib "eagle-import") (part "TPTP16R"))
    )
    (comp (ref "U7")
      (value "TL074")
      (footprint "eagle-import:SOIC127P600X175-14N")
      (libsource (lib "eagle-import") (part "LM324BD"))
    )
    (comp (ref "U8")
      (value "LM13700")
      (footprint "eagle-import:SO16")
      (libsource (lib "eagle-import") (part "LM13700"))
    )
  )
  (nets
    (net (code "10") (name "+3V3") (class "Default")
      (node (ref "C23") (pin "P$1") (pinfunction "1_P$1") (pintype "passive"))
      (node (ref "C24") (pin "P$1") (pinfunction "1_P$1") (pintype "passive"))
      (node (ref "C26") (pin "P$1") (pinfunction "1_P$1") (pintype "passive"))
      (node (ref "C28") (pin "P$1") (pinfunction "1_P$1") (pintype "passive"))
      (node (ref "C29") (pin "P$1") (pinfunction "1_P$1") (pintype "passive"))
      (node (ref "C33") (pin "P$1") (pinfunction "1_P$1") (pintype "passive"))
      (node (ref "D4") (pin "A") (pinfunction "A_A") (pintype "bidirectional"))
      (node (ref "J2") (pin "4") (pinfunction "4_4") (pintype "bidirectional"))
      (node (ref "J3") (pin "03") (pinfunction "03_03") (pintype "passive"))
      (node (ref "R10") (pin "2") (pinfunction "2_2") (pintype "passive"))
      (node (ref "R11") (pin "2") (pinfunction "2_2") (pintype "passive"))
      (node (ref "R13") (pin "2") (pinfunction "2_2") (pintype "passive"))
      (node (ref "R8") (pin "2") (pinfunction "2_2") (pintype "passive"))
      (node (ref "R9") (pin "2") (pinfunction "2_2") (pintype "passive"))
      (node (ref "SJ1") (pin "1") (pinfunction "1_1") (pintype "passive"))
      (node (ref "SJ6") (pin "NO") (pinfunction "NO_NO") (pintype "passive"))
      (node (ref "U5") (pin "5") (pinfunction "VCC_5") (pintype "power_in"))
      (node (ref "U6") (pin "17") (pinfunction "VDD_17") (pintype "power_in"))
      (node (ref "U6") (pin "48") (pinfunction "VDD_48") (pintype "power_in"))
    )
    (net (code "11") (name "+3V3A") (class "Default")
      (node (ref "C30") (pin "P$1") (pinfunction "1_P$1") (pintype "passive"))
      (node (ref "C31") (pin "P$1") (pinfunction "1_P$1") (pintype "passive"))
      (node (ref "C32") (pin "P$1") (pinfunction "1_P$1") (pintype "passive"))
      (node (ref "D14") (pin "C") (pinfunction "K_C") (pintype "bidirectional"))
      (node (ref "D4") (pin "C") (pinfunction "K_C") (pintype "bidirectional"))
      (node (ref "J6") (pin "14") (pinfunction "14_14") (pintype "bidirectional"))
      (node (ref "J6") (pin "7") (pinfunction "7_7") (pintype "bidirectional"))
      (node (ref "R17") (pin "2") (pinfunction "2_2") (pintype "passive"))
      (node (ref "R19") (pin "P$3") (pinfunction "2_P$3") (pintype "passive"))
      (node (ref "R31") (pin "2") (pinfunction "2_2") (pintype "passive"))
      (node (ref "SJ2") (pin "1") (pinfunction "1_1") (pintype "passive"))
      (node (ref "SJ3") (pin "1") (pinfunction "1_1") (pintype "passive"))
      (node (ref "U6") (pin "24") (pinfunction "VDDSD_24") (pintype "power_in"))
      (node (ref "U6") (pin "9") (pinfunction "VDDA/VREF+_9") (pintype "input"))
    )
    (net (code "12") (name "+5V") (class "Default")
      (node (ref "C13") (pin "P$1") (pinfunction "1_P$1") (pintype "passive"))
      (node (ref "C14") (pin "A") (pinfunction "+_A") (pintype "passive"))
      (node (ref "C15") (pin "P$1") (pinfunction "1_P$1") (pintype "passive"))
      (node (ref "C19") (pin "P$1") (pinfunction "1_P$1") (pintype "passive"))
      (node (ref "C36") (pin "P$1") (pinfunction "1_P$1") (pintype "passive"))
      (node (ref "C38") (pin "P$1") (pinfunction "1_P$1") (pintype "passive"))
      (node (ref "C6") (pin "P$1") (pinfunction "1_P$1") (pintype "passive"))
      (node (ref "C9") (pin "+") (pinfunction "+_+") (pintype "passive"))
      (node (ref "D10") (pin "C") (pinfunction "K_C") (pintype "bidirectional"))
      (node (ref "D12") (pin "A") (pinfunction "A_A") (pintype "bidirectional"))
      (node (ref "D6") (pin "C") (pinfunction "K_C") (pintype "bidirectional"))
      (node (ref "J6") (pin "1") (pinfunction "1_1") (pintype "bidirectional"))
      (node (ref "J6") (pin "9") (pinfunction "9_9") (pintype "bidirectional"))
      (node (ref "PS1") (pin "+VOUT") (pinfunction "+VOUT_+VOUT") (pintype "passive"))
      (node (ref "R28") (pin "2") (pinfunction "2_2") (pintype "passive"))
      (node (ref "R37") (pin "1") (pinfunction "1_1") (pintype "passive"))
      (node (ref "R7") (pin "2") (pinfunction "2_2") (pintype "passive"))
      (node (ref "SJ6") (pin "NC") (pinfunction "NC_NC") (pintype "passive"))
      (node (ref "TP1") (pin "1") (pinfunction "P_1") (pintype "bidirectional"))
      (node (ref "U2") (pin "8") (pinfunction "VCC2_8") (pintype "power_in"))
      (node (ref "U3") (pin "1") (pinfunction "IN_1") (pintype "power_in"))
      (node (ref "U4") (pin "1") (pinfunction "IN_1") (pintype "power_in"))
      (node (ref "U4") (pin "3") (pinfunction "EN_3") (pintype "input"))
      (node (ref "U7") (pin "4") (pinfunction "V+_4") (pintype "power_in"))
      (node (ref "U8") (pin "11") (pinfunction "V+_11") (pintype "power_in"))
    )
    (net (code "13") (name "-5V") (class "Default")
      (node (ref "C10") (pin "-") (pinfunction "-_-") (pintype "passive"))
      (node (ref "C37") (pin "P$2") (pinfunction "2_P$2") (pintype "passive"))
      (node (ref "C39") (pin "P$2") (pinfunction "2_P$2") (pintype "passive"))
      (node (ref "C7") (pin "P$2") (pinfunction "2_P$2") (pintype "passive"))
      (node (ref "D11") (pin "A") (pinfunction "A_A") (pintype "bidirectional"))
      (node (ref "D7") (pin "A") (pinfunction "A_A") (pintype "bidirectional"))
      (node (ref "J6") (pin "2") (pinfunction "2_2") (pintype "bidirectional"))
      (node (ref "J6") (pin "8") (pinfunction "8_8") (pintype "bidirectional"))
      (node (ref "PS2") (pin "-VOUT") (pinfunction "-VOUT_-VOUT") (pintype "passive"))
      (node (ref "TP4") (pin "1") (pinfunction "P_1") (pintype "bidirectional"))
      (node (ref "U7") (pin "11") (pinfunction "V-_11") (pintype "power_in"))
      (node (ref "U8") (pin "16") (pinfunction "AMP_BIAS_16") (pintype "bidirectional"))
      (node (ref "U8") (pin "6") (pinfunction "V-_6") (pintype "power_in"))
    )
    (net (code "20") (name "ACQ_LED") (class "Default")
      (node (ref "J5") (pin "P$4") (pinfunction "4_P$4") (pintype "bidirectional"))
      (node (ref "R38") (pin "1") (pinfunction "1_1") (pintype "passive"))
      (node (ref "U6") (pin "42") (pinfunction "PB6_42") (pintype "bidirectional"))
    )
    (net (code "21") (name "BOOT0") (class "Default")
      (node (ref "J5") (pin "P$3") (pinfunction "3_P$3") (pintype "bidirectional"))
      (node (ref "R12") (pin "1") (pinfunction "1_1") (pintype "passive"))
      (node (ref "R14") (pin "1") (pinfunction "1_1") (pintype "passive"))
      (node (ref "U5") (pin "4") (pinfunction "Q_4") (pintype "output"))
      (node (ref "U6") (pin "44") (pinfunction "BOOT0_44") (pintype "bidirectional"))
    )
    (net (code "22") (name "DAC1_CH1") (class "Default")
      (node (ref "R18") (pin "2") (pinfunction "2_2") (pintype "passive"))
      (node (ref "TP7") (pin "TP") (pinfunction "TP_TP") (pintype "input"))
      (node (ref "U6") (pin "13") (pinfunction "PA3_13") (pintype "bidirectional"))
    )
    (net (code "23") (name "DAC1_CH2") (class "Default")
      (node (ref "J6") (pin "12") (pinfunction "12_12") (pintype "bidirectional"))
      (node (ref "U6") (pin "14") (pinfunction "PA4_14") (pintype "bidirectional"))
    )
    (net (code "24") (name "DAC2_CH1") (class "Default")
      (node (ref "J6") (pin "5") (pinfunction "5_5") (pintype "bidirectional"))
      (node (ref "U6") (pin "15") (pinfunction "PA5_15") (pintype "bidirectional"))
    )
    (net (code "25") (name "FF_CLK") (class "Default")
      (node (ref "U5") (pin "1") (pinfunction "CLK_1") (pintype "input"))
      (node (ref "U6") (pin "46") (pinfunction "PB9_46") (pintype "bidirectional"))
    )
    (net (code "26") (name "FF_CLR") (class "Default")
      (node (ref "C22") (pin "P$1") (pinfunction "1_P$1") (pintype "passive"))
      (node (ref "R8") (pin "1") (pinfunction "1_1") (pintype "passive"))
      (node (ref "U5") (pin "6") (pinfunction "~{CLR}_6") (pintype "input"))
    )
    (net (code "27") (name "FF_D") (class "Default")
      (node (ref "U5") (pin "3") (pinfunction "D_3") (pintype "input"))
      (node (ref "U6") (pin "45") (pinfunction "PB8_45") (pintype "bidirectional"))
    )
    (net (code "28") (name "GND") (class "Default")
      (node (ref "C10") (pin "+") (pinfunction "+_+") (pintype "passive"))
      (node (ref "C13") (pin "P$2") (pinfunction "2_P$2") (pintype "passive"))
      (node (ref "C14") (pin "K") (pinfunction "-_K") (pintype "passive"))
      (node (ref "C15") (pin "P$2") (pinfunction "2_P$2") (pintype "passive"))
      (node (ref "C16") (pin "P$2") (pinfunction "2_P$2") (pintype "passive"))
      (node (ref "C17") (pin "P$2") (pinfunction "2_P$2") (pintype "passive"))
      (node (ref "C18") (pin "P$2") (pinfunction "2_P$2") (pintype "passive"))
      (node (ref "C19") (pin "P$2") (pinfunction "2_P$2") (pintype "passive"))
      (node (ref "C20") (pin "P$2") (pinfunction "2_P$2") (pintype "passive"))
      (node (ref "C21") (pin "P$2") (pinfunction "2_P$2") (pintype "passive"))
      (node (ref "C22") (pin "P$2") (pinfunction "2_P$2") (pintype "passive"))
      (node (ref "C24") (pin "P$2") (pinfunction "2_P$2") (pintype "passive"))
      (node (ref "C25") (pin "P$2") (pinfunction "2_P$2") (pintype "passive"))
      (node (ref "C26") (pin "P$2") (pinfunction "2_P$2") (pintype "passive"))
      (node (ref "C27") (pin "P$2") (pinfunction "2_P$2") (pintype "passive"))
      (node (ref "C28") (pin "P$2") (pinfunction "2_P$2") (pintype "passive"))
      (node (ref "C29") (pin "P$2") (pinfunction "2_P$2") (pintype "passive"))
      (node (ref "C30") (pin "P$2") (pinfunction "2_P$2") (pintype "passive"))
      (node (ref "C31") (pin "P$2") (pinfunction "2_P$2") (pintype "passive"))
      (node (ref "C32") (pin "P$2") (pinfunction "2_P$2") (pintype "passive"))
      (node (ref "C33") (pin "P$2") (pinfunction "2_P$2") (pintype "passive"))
      (node (ref "C34") (pin "P$2") (pinfunction "2_P$2") (pintype "passive"))
      (node (ref "C35") (pin "P$2") (pinfunction "2_P$2") (pintype "passive"))
      (node (ref "C36") (pin "P$2") (pinfunction "2_P$2") (pintype "passive"))
      (node (ref "C37") (pin "P$1") (pinfunction "1_P$1") (pintype "passive"))
      (node (ref "C38") (pin "P$2") (pinfunction "2_P$2") (pintype "passive"))
      (node (ref "C39") (pin "P$1") (pinfunction "1_P$1") (pintype "passive"))
      (node (ref "C40") (pin "P$2") (pinfunction "2_P$2") (pintype "passive"))
      (node (ref "C6") (pin "P$2") (pinfunction "2_P$2") (pintype "passive"))
      (node (ref "C7") (pin "P$1") (pinfunction "1_P$1") (pintype "passive"))
      (node (ref "C9") (pin "-") (pinfunction "-_-") (pintype "passive"))
      (node (ref "D15") (pin "A") (pinfunction "A_A") (pintype "bidirectional"))
      (node (ref "D16") (pin "K") (pinfunction "K_K") (pintype "passive"))
      (node (ref "D17") (pin "K") (pinfunction "K_K") (pintype "passive"))
      (node (ref "D5") (pin "K") (pinfunction "K_K") (pintype "passive"))
      (node (ref "J2") (pin "2") (pinfunction "2_2") (pintype "bidirectional"))
      (node (ref "J3") (pin "05") (pinfunction "05_05") (pintype "passive"))
      (node (ref "J3") (pin "07") (pinfunction "07_07") (pintype "passive"))
      (node (ref "J4") (pin "1") (pinfunction "SLEEVE_1") (pintype "passive"))
      (node (ref "J5") (pin "P$1") (pinfunction "1_P$1") (pintype "bidirectional"))
      (node (ref "J5") (pin "P$7") (pinfunction "SUP_P$7") (pintype "bidirectional"))
      (node (ref "J5") (pin "P$8") (pinfunction "SUP_P$8") (pintype "bidirectional"))
      (node (ref "J6") (pin "13") (pinfunction "13_13") (pintype "bidirectional"))
      (node (ref "J6") (pin "6") (pinfunction "6_6") (pintype "bidirectional"))
      (node (ref "PS1") (pin "-VOUT") (pinfunction "-VOUT_-VOUT") (pintype "passive"))
      (node (ref "PS2") (pin "+VOUT") (pinfunction "+VOUT_+VOUT") (pintype "passive"))
      (node (ref "R14") (pin "2") (pinfunction "2_2") (pintype "passive"))
      (node (ref "R19") (pin "P$1") (pinfunction "1_P$1") (pintype "passive"))
      (node (ref "R22") (pin "1") (pinfunction "1_1") (pintype "passive"))
      (node (ref "R26") (pin "1") (pinfunction "1_1") (pintype "passive"))
      (node (ref "R27") (pin "2") (pinfunction "2_2") (pintype "passive"))
      (node (ref "R32") (pin "3") (pinfunction "2_3") (pintype "passive"))
      (node (ref "R33") (pin "2") (pinfunction "2_2") (pintype "passive"))
      (node (ref "R34") (pin "2") (pinfunction "2_2") (pintype "passive"))
      (node (ref "S1") (pin "P$3") (pinfunction "P$2_P$3") (pintype "bidirectional"))
      (node (ref "S1") (pin "P$4") (pinfunction "P$2_P$4") (pintype "bidirectional"))
      (node (ref "SHIELD1") (pin "P$1") (pinfunction "1_P$1") (pintype "bidirectional"))
      (node (ref "SHIELD1") (pin "P$2") (pinfunction "1_P$2") (pintype "bidirectional"))
      (node (ref "SJ5") (pin "NO") (pinfunction "NO_NO") (pintype "passive"))
      (node (ref "SW1") (pin "P$2") (pinfunction "P$2_P$2") (pintype "passive"))
      (node (ref "SW1") (pin "P$4") (pinfunction "P$4_P$4") (pintype "passive"))
      (node (ref "SW1") (pin "P$6") (pinfunction "P$6_P$6") (pintype "passive"))
      (node (ref "TP2") (pin "1") (pinfunction "P_1") (pintype "bidirectional"))
      (node (ref "U2") (pin "5") (pinfunction "GND2_5") (pintype "power_in"))
      (node (ref "U3") (pin "2") (pinfunction "GND_2") (pintype "power_in"))
      (node (ref "U4") (pin "2") (pinfunction "GND_2") (pintype "power_in"))
      (node (ref "U5") (pin "2") (pinfunction "GND_2") (pintype "power_in"))
      (node (ref "U6") (pin "23") (pinfunction "VSSD/VREFSD-_23") (pintype "input"))
      (node (ref "U6") (pin "47") (pinfunction "VSS_47") (pintype "power_in"))
      (node (ref "U6") (pin "8") (pinfunction "VSSA/VREF-_8") (pintype "input"))
      (node (ref "U7") (pin "12") (pinfunction "+IN_12") (pintype "input"))
      (node (ref "U7") (pin "5") (pinfunction "+IN_5") (pintype "input"))
    )
    (net (code "29") (name "GND-1") (class "Default")
      (node (ref "C1") (pin "P$2") (pinfunction "2_P$2") (pintype "passive"))
      (node (ref "C11") (pin "P$2") (pinfunction "2_P$2") (pintype "passive"))
      (node (ref "C12") (pin "P$2") (pinfunction "2_P$2") (pintype "passive"))
      (node (ref "C2") (pin "P$2") (pinfunction "2_P$2") (pintype "passive"))
      (node (ref "C3") (pin "P$2") (pinfunction "2_P$2") (pintype "passive"))
      (node (ref "C4") (pin "P$2") (pinfunction "2_P$2") (pintype "passive"))
      (node (ref "C5") (pin "P$2") (pinfunction "2_P$2") (pintype "passive"))
      (node (ref "C8") (pin "P$2") (pinfunction "2_P$2") (pintype "passive"))
      (node (ref "D1") (pin "C") (pinfunction "P$2_C") (pintype "bidirectional"))
      (node (ref "D2") (pin "C") (pinfunction "P$2_C") (pintype "bidirectional"))
      (node (ref "D3") (pin "C") (pinfunction "P$2_C") (pintype "bidirectional"))
      (node (ref "J1") (pin "4") (pinfunction "GND_4") (pintype "power_in"))
      (node (ref "PS1") (pin "-VIN") (pinfunction "-VIN_-VIN") (pintype "passive"))
      (node (ref "PS2") (pin "-VIN") (pinfunction "-VIN_-VIN") (pintype "passive"))
      (node (ref "R1") (pin "2") (pinfunction "2_2") (pintype "passive"))
      (node (ref "R3") (pin "2") (pinfunction "2_2") (pintype "passive"))
      (node (ref "U1") (pin "3") (pinfunction "GND_3") (pintype "power_in"))
      (node (ref "U1") (pin "EXP") (pinfunction "GND_EXP") (pintype "power_in"))
      (node (ref "U2") (pin "4") (pinfunction "GND1_4") (pintype "power_in"))
    )
    (net (code "30") (name "I_ABC") (class "Default")
      (node (ref "Q1") (pin "3") (pinfunction "C_3") (pintype "passive"))
      (node (ref "U8") (pin "1") (pinfunction "AMP_BIAS_1") (pintype "bidirectional"))
    )
    (net (code "31") (name "JCLK") (class "Default")
      (node (ref "J2") (pin "3") (pinfunction "3_3") (pintype "bidirectional"))
      (node (ref "J3") (pin "06") (pinfunction "06_06") (pintype "passive"))
      (node (ref "SJ4") (pin "2") (pinfunction "2_2") (pintype "passive"))
      (node (ref "U6") (pin "37") (pinfunction "PA14_37") (pintype "bidirectional"))
    )
    (net (code "32") (name "JRCLK") (class "Default")
      (node (ref "J3") (pin "09") (pinfunction "09_09") (pintype "passive"))
      (node (ref "SJ4") (pin "1") (pinfunction "1_1") (pintype "passive"))
    )
    (net (code "33") (name "JTDI") (class "Default")
      (node (ref "J3") (pin "10") (pinfunction "10_10") (pintype "passive"))
      (node (ref "U6") (pin "38") (pinfunction "PA15_38") (pintype "bidirectional"))
    )
    (net (code "34") (name "JTDO") (class "Default")
      (node (ref "J3") (pin "08") (pinfunction "08_08") (pintype "passive"))
      (node (ref "U6") (pin "39") (pinfunction "PB3_39") (pintype "bidirectional"))
    )
    (net (code "35") (name "JTMS") (class "Default")
      (node (ref "J2") (pin "1") (pinfunction "1_1") (pintype "bidirectional"))
      (node (ref "J3") (pin "04") (pinfunction "04_04") (pintype "passive"))
      (node (ref "U6") (pin "34") (pinfunction "PA13_34") (pintype "bidirectional"))
    )
    (net (code "36") (name "MCU_RX") (class "Default")
      (node (ref "J3") (pin "13") (pinfunction "13_13") (pintype "passive"))
      (node (ref "R15") (pin "2") (pinfunction "2_2") (pintype "passive"))
    )
    (net (code "37") (name "MCU_TX") (class "Default")
      (node (ref "J3") (pin "14") (pinfunction "14_14") (pintype "passive"))
      (node (ref "R16") (pin "2") (pinfunction "2_2") (pintype "passive"))
    )
    (net (code "38") (name "NRST") (class "Default")
      (node (ref "C23") (pin "P$2") (pinfunction "2_P$2") (pintype "passive"))
      (node (ref "J3") (pin "12") (pinfunction "12_12") (pintype "passive"))
      (node (ref "R9") (pin "1") (pinfunction "1_1") (pintype "passive"))
      (node (ref "S1") (pin "P$1") (pinfunction "P$1_P$1") (pintype "bidirectional"))
      (node (ref "S1") (pin "P$2") (pinfunction "P$1_P$2") (pintype "bidirectional"))
      (node (ref "U6") (pin "7") (pinfunction "NRST_7") (pintype "input"))
    )
    (net (code "39") (name "Net-(C3-1)") (class "Default")
      (node (ref "C3") (pin "P$1") (pinfunction "1_P$1") (pintype "passive"))
      (node (ref "J1") (pin "M1") (pinfunction "SHIELD_M1") (pintype "power_in"))
      (node (ref "J1") (pin "M2") (pinfunction "SHIELD_M2") (pintype "power_in"))
      (node (ref "R1") (pin "1") (pinfunction "1_1") (pintype "passive"))
    )
    (net (code "40") (name "Net-(C16-1)") (class "Default")
      (node (ref "C16") (pin "P$1") (pinfunction "1_P$1") (pintype "passive"))
      (node (ref "R7") (pin "1") (pinfunction "1_1") (pintype "passive"))
      (node (ref "U3") (pin "3") (pinfunction "EN_3") (pintype "input"))
    )
    (net (code "41") (name "Net-(C17-1)") (class "Default")
      (node (ref "C17") (pin "P$1") (pinfunction "1_P$1") (pintype "passive"))
      (node (ref "C18") (pin "P$1") (pinfunction "1_P$1") (pintype "passive"))
      (node (ref "SJ1") (pin "2") (pinfunction "2_2") (pintype "passive"))
      (node (ref "TP3") (pin "1") (pinfunction "P_1") (pintype "bidirectional"))
      (node (ref "U3") (pin "5") (pinfunction "OUT_5") (pintype "power_in"))
    )
    (net (code "42") (name "Net-(C20-1)") (class "Default")
      (node (ref "C20") (pin "P$1") (pinfunction "1_P$1") (pintype "passive"))
      (node (ref "C21") (pin "P$1") (pinfunction "1_P$1") (pintype "passive"))
      (node (ref "SJ2") (pin "2") (pinfunction "2_2") (pintype "passive"))
      (node (ref "U4") (pin "5") (pinfunction "OUT_5") (pintype "power_in"))
    )
    (net (code "43") (name "Net-(C40-1)") (class "Default")
      (node (ref "C40") (pin "P$1") (pinfunction "1_P$1") (pintype "passive"))
      (node (ref "R21") (pin "1") (pinfunction "1_1") (pintype "passive"))
      (node (ref "R22") (pin "2") (pinfunction "2_2") (pintype "passive"))
      (node (ref "U7") (pin "3") (pinfunction "+IN_3") (pintype "input"))
    )
    (net (code "44") (name "Net-(C41-1)") (class "Default")
      (node (ref "C41") (pin "P$1") (pinfunction "1_P$1") (pintype "passive"))
      (node (ref "R20") (pin "1") (pinfunction "1_1") (pintype "passive"))
      (node (ref "R23") (pin "2") (pinfunction "2_2") (pintype "passive"))
      (node (ref "U7") (pin "2") (pinfunction "-IN_2") (pintype "input"))
    )
    (net (code "45") (name "Net-(C42-1)") (class "Default")
      (node (ref "C42") (pin "P$1") (pinfunction "1_P$1") (pintype "passive"))
      (node (ref "C43") (pin "1") (pinfunction "+_1") (pintype "passive"))
      (node (ref "R24") (pin "2") (pinfunction "2_2") (pintype "passive"))
      (node (ref "SJ7") (pin "P$1") (pinfunction "P$1_P$1") (pintype "bidirectional"))
      (node (ref "TP5") (pin "TP") (pinfunction "TP_TP") (pintype "input"))
      (node (ref "U7") (pin "14") (pinfunction "OUT_14") (pintype "output"))
    )
    (net (code "46") (name "Net-(C43--)") (class "Default")
      (node (ref "C43") (pin "2") (pinfunction "-_2") (pintype "passive"))
      (node (ref "R35") (pin "1") (pinfunction "1_1") (pintype "passive"))
      (node (ref "SJ7") (pin "P$2") (pinfunction "P$2_P$2") (pintype "bidirectional"))
    )
    (net (code "47") (name "Net-(D2-P$1)") (class "Default")
      (node (ref "D2") (pin "A") (pinfunction "P$1_A") (pintype "bidirectional"))
      (node (ref "J1") (pin "3") (pinfunction "D+_3") (pintype "bidirectional"))
      (node (ref "U1") (pin "4") (pinfunction "D+_4") (pintype "bidirectional"))
    )
    (net (code "48") (name "Net-(D3-P$1)") (class "Default")
      (node (ref "D3") (pin "A") (pinfunction "P$1_A") (pintype "bidirectional"))
      (node (ref "J1") (pin "2") (pinfunction "D-_2") (pintype "bidirectional"))
      (node (ref "U1") (pin "5") (pinfunction "D-_5") (pintype "bidirectional"))
    )
    (net (code "49") (name "Net-(D5-PadA)") (class "Default")
      (node (ref "D5") (pin "A") (pinfunction "A_A") (pintype "passive"))
      (node (ref "R12") (pin "2") (pinfunction "2_2") (pintype "passive"))
    )
    (net (code "50") (name "Net-(D7-K)") (class "Default")
      (node (ref "D6") (pin "A") (pinfunction "A_A") (pintype "bidirectional"))
      (node (ref "D7") (pin "C") (pinfunction "K_C") (pintype "bidirectional"))
      (node (ref "D8") (pin "A") (pinfunction "A_A") (pintype "bidirectional"))
      (node (ref "D9") (pin "C") (pinfunction "K_C") (pintype "bidirectional"))
      (node (ref "R21") (pin "2") (pinfunction "2_2") (pintype "passive"))
      (node (ref "SJ5") (pin "NC") (pinfunction "NC_NC") (pintype "passive"))
    )
    (net (code "51") (name "Net-(D11-K)") (class "Default")
      (node (ref "D10") (pin "A") (pinfunction "A_A") (pintype "bidirectional"))
      (node (ref "D11") (pin "C") (pinfunction "K_C") (pintype "bidirectional"))
      (node (ref "D8") (pin "C") (pinfunction "K_C") (pintype "bidirectional"))
      (node (ref "D9") (pin "A") (pinfunction "A_A") (pintype "bidirectional"))
      (node (ref "J4") (pin "2") (pinfunction "TIP_2") (pintype "passive"))
      (node (ref "R20") (pin "2") (pinfunction "2_2") (pintype "passive"))
    )
    (net (code "52") (name "Net-(D12-K)") (class "Default")
      (node (ref "D12") (pin "C") (pinfunction "K_C") (pintype "bidirectional"))
      (node (ref "D13") (pin "A") (pinfunction "A_A") (pintype "bidirectional"))
    )
    (net (code "53") (name "Net-(D13-K)") (class "Default")
      (node (ref "D13") (pin "C") (pinfunction "K_C") (pintype "bidirectional"))
      (node (ref "Q2") (pin "1") (pinfunction "B_1") (pintype "passive"))
      (node (ref "R26") (pin "2") (pinfunction "2_2") (pintype "passive"))
    )
    (net (code "54") (name "Net-(D16-PadA)") (class "Default")
      (node (ref "D16") (pin "A") (pinfunction "A_A") (pintype "passive"))
      (node (ref "R37") (pin "2") (pinfunction "2_2") (pintype "passive"))
    )
    (net (code "55") (name "Net-(D17-PadA)") (class "Default")
      (node (ref "D17") (pin "A") (pinfunction "A_A") (pintype "passive"))
      (node (ref "R38") (pin "2") (pinfunction "2_2") (pintype "passive"))
    )
    (net (code "56") (name "Net-(J4-RING)") (class "Default")
      (node (ref "J4") (pin "3") (pinfunction "RING_3") (pintype "passive"))
      (node (ref "SJ5") (pin "COM") (pinfunction "COM_COM") (pintype "passive"))
    )
    (net (code "57") (name "Net-(J5-2)") (class "Default")
      (node (ref "J5") (pin "P$2") (pinfunction "2_P$2") (pintype "bidirectional"))
      (node (ref "SJ6") (pin "COM") (pinfunction "COM_COM") (pintype "passive"))
    )
    (net (code "58") (name "Net-(Q1-B)") (class "Default")
      (node (ref "Q1") (pin "1") (pinfunction "B_1") (pintype "passive"))
      (node (ref "U7") (pin "7") (pinfunction "OUT_7") (pintype "output"))
    )
    (net (code "59") (name "Net-(Q1-E)") (class "Default")
      (node (ref "Q1") (pin "2") (pinfunction "E_2") (pintype "passive"))
      (node (ref "R17") (pin "1") (pinfunction "1_1") (pintype "passive"))
      (node (ref "R18") (pin "1") (pinfunction "1_1") (pintype "passive"))
      (node (ref "U7") (pin "6") (pinfunction "-IN_6") (pintype "input"))
    )
    (net (code "60") (name "Net-(Q2-C)") (class "Default")
      (node (ref "Q2") (pin "3") (pinfunction "C_3") (pintype "passive"))
      (node (ref "U8") (pin "2") (pinfunction "D_BIAS_2") (pintype "bidirectional"))
    )
    (net (code "61") (name "Net-(Q2-E)") (class "Default")
      (node (ref "Q2") (pin "2") (pinfunction "E_2") (pintype "passive"))
      (node (ref "R28") (pin "1") (pinfunction "1_1") (pintype "passive"))
    )
    (net (code "62") (name "Net-(R29-Pad1)") (class "Default")
      (node (ref "R29") (pin "1") (pinfunction "1_1") (pintype "passive"))
      (node (ref "R30") (pin "1") (pinfunction "1_1") (pintype "passive"))
    )
    (net (code "63") (name "Net-(R29-Pad2)") (class "Default")
      (node (ref "R29") (pin "2") (pinfunction "2_2") (pintype "passive"))
      (node (ref "R33") (pin "1") (pinfunction "1_1") (pintype "passive"))
      (node (ref "R34") (pin "1") (pinfunction "1_1") (pintype "passive"))
    )
    (net (code "64") (name "Net-(R30-2)") (class "Default")
      (node (ref "R30") (pin "2") (pinfunction "C_2") (pintype "bidirectional"))
      (node (ref "R30") (pin "3") (pinfunction "2_3") (pintype "passive"))
      (node (ref "U8") (pin "4") (pinfunction "-_4") (pintype "bidirectional"))
    )
    (net (code "65") (name "Net-(R31-Pad1)") (class "Default")
      (node (ref "R31") (pin "1") (pinfunction "1_1") (pintype "passive"))
      (node (ref "R32") (pin "1") (pinfunction "1_1") (pintype "passive"))
    )
    (net (code "66") (name "Net-(R32-C)") (class "Default")
      (node (ref "R32") (pin "2") (pinfunction "C_2") (pintype "bidirectional"))
      (node (ref "U7") (pin "10") (pinfunction "+IN_10") (pintype "input"))
    )
    (net (code "67") (name "Net-(U1-~{RST})") (class "Default")
      (node (ref "R4") (pin "2") (pinfunction "2_2") (pintype "passive"))
      (node (ref "U1") (pin "9") (pinfunction "~{RST}_9") (pintype "bidirectional"))
    )
    (net (code "68") (name "Net-(U7C--IN)") (class "Default")
      (node (ref "R35") (pin "2") (pinfunction "2_2") (pintype "passive"))
      (node (ref "R36") (pin "1") (pinfunction "1_1") (pintype "passive"))
      (node (ref "U7") (pin "9") (pinfunction "-IN_9") (pintype "input"))
    )
    (net (code "69") (name "Net-(U8A-+)") (class "Default")
      (node (ref "R25") (pin "2") (pinfunction "2_2") (pintype "passive"))
      (node (ref "R27") (pin "1") (pinfunction "1_1") (pintype "passive"))
      (node (ref "U8") (pin "3") (pinfunction "+_3") (pintype "bidirectional"))
    )
    (net (code "70") (name "OSC2_IN") (class "Default")
      (node (ref "C25") (pin "P$1") (pinfunction "1_P$1") (pintype "passive"))
      (node (ref "U6") (pin "5") (pinfunction "PF0/OSC_IN_5") (pintype "bidirectional"))
      (node (ref "XTAL1") (pin "P$3") (pinfunction "X2_P$3") (pintype "passive"))
    )
    (net (code "71") (name "OSC2_OUT") (class "Default")
      (node (ref "C27") (pin "P$1") (pinfunction "1_P$1") (pintype "passive"))
      (node (ref "U6") (pin "6") (pinfunction "PF1/OSC_OUT_6") (pintype "bidirectional"))
      (node (ref "XTAL1") (pin "P$1") (pinfunction "X1_P$1") (pintype "passive"))
    )
    (net (code "72") (name "OUT_CHARGE_AMP") (class "Default")
      (node (ref "C41") (pin "P$2") (pinfunction "2_P$2") (pintype "passive"))
      (node (ref "R23") (pin "1") (pinfunction "1_1") (pintype "passive"))
      (node (ref "R25") (pin "1") (pinfunction "1_1") (pintype "passive"))
      (node (ref "TP8") (pin "TP") (pinfunction "TP_TP") (pintype "input"))
      (node (ref "U7") (pin "1") (pinfunction "OUT_1") (pintype "output"))
    )
    (net (code "73") (name "OUT_OTA") (class "Default")
      (node (ref "C42") (pin "P$2") (pinfunction "2_P$2") (pintype "passive"))
      (node (ref "R24") (pin "1") (pinfunction "1_1") (pintype "passive"))
      (node (ref "U7") (pin "13") (pinfunction "-IN_13") (pintype "input"))
      (node (ref "U8") (pin "5") (pinfunction "OUT_5") (pintype "bidirectional"))
    )
    (net (code "74") (name "POWER_LED") (class "Default")
      (node (ref "J5") (pin "P$5") (pinfunction "5_P$5") (pintype "bidirectional"))
      (node (ref "U6") (pin "43") (pinfunction "PB7_43") (pintype "bidirectional"))
    )
    (net (code "75") (name "RXD") (class "Default")
      (node (ref "U1") (pin "25") (pinfunction "RXD_25") (pintype "input"))
      (node (ref "U2") (pin "2") (pinfunction "OUT_A_2") (pintype "output"))
    )
    (net (code "76") (name "SDADC1_CH4") (class "Default")
      (node (ref "J6") (pin "3") (pinfunction "3_3") (pintype "bidirectional"))
      (node (ref "U6") (pin "20") (pinfunction "PB2_20") (pintype "bidirectional"))
    )
    (net (code "77") (name "SDADC1_CH5") (class "Default")
      (node (ref "D14") (pin "A") (pinfunction "A_A") (pintype "bidirectional"))
      (node (ref "D15") (pin "C") (pinfunction "K_C") (pintype "bidirectional"))
      (node (ref "R36") (pin "2") (pinfunction "2_2") (pintype "passive"))
      (node (ref "TP6") (pin "TP") (pinfunction "TP_TP") (pintype "input"))
      (node (ref "U6") (pin "19") (pinfunction "PB1_19") (pintype "bidirectional"))
      (node (ref "U7") (pin "8") (pinfunction "OUT_8") (pintype "output"))
    )
    (net (code "78") (name "SDADC1_CH6") (class "Default")
      (node (ref "R19") (pin "P$2") (pinfunction "C_P$2") (pintype "bidirectional"))
      (node (ref "TP10") (pin "TP") (pinfunction "TP_TP") (pintype "input"))
      (node (ref "U6") (pin "18") (pinfunction "PB0_18") (pintype "bidirectional"))
    )
    (net (code "79") (name "SDADC1_CH7") (class "Default")
      (node (ref "TP9") (pin "TP") (pinfunction "TP_TP") (pintype "input"))
      (node (ref "U6") (pin "22") (pinfunction "PE9_22") (pintype "bidirectional"))
    )
    (net (code "80") (name "SDADC1_CH8") (class "Default")
      (node (ref "J6") (pin "4") (pinfunction "4_4") (pintype "bidirectional"))
      (node (ref "U6") (pin "21") (pinfunction "PE8_21") (pintype "bidirectional"))
    )
    (net (code "81") (name "SDADC3_CH7") (class "Default")
      (node (ref "J6") (pin "10") (pinfunction "10_10") (pintype "bidirectional"))
      (node (ref "U6") (pin "27") (pinfunction "PB15_27") (pintype "bidirectional"))
    )
    (net (code "82") (name "SDADC3_CH8") (class "Default")
      (node (ref "J6") (pin "11") (pinfunction "11_11") (pintype "bidirectional"))
      (node (ref "U6") (pin "26") (pinfunction "PB14_26") (pintype "bidirectional"))
    )
    (net (code "83") (name "SW_1") (class "Default")
      (node (ref "R10") (pin "1") (pinfunction "1_1") (pintype "passive"))
      (node (ref "SW1") (pin "P$1") (pinfunction "P$1_P$1") (pintype "passive"))
      (node (ref "U6") (pin "2") (pinfunction "PC13_2") (pintype "bidirectional"))
    )
    (net (code "84") (name "SW_2") (class "Default")
      (node (ref "R11") (pin "1") (pinfunction "1_1") (pintype "passive"))
      (node (ref "SW1") (pin "P$3") (pinfunction "P$3_P$3") (pintype "passive"))
      (node (ref "U6") (pin "3") (pinfunction "PC14/OSC32_IN_3") (pintype "bidirectional"))
    )
    (net (code "85") (name "SW_3") (class "Default")
      (node (ref "R13") (pin "1") (pinfunction "1_1") (pintype "passive"))
      (node (ref "SW1") (pin "P$5") (pinfunction "P$5_P$5") (pintype "passive"))
      (node (ref "U6") (pin "4") (pinfunction "PC15/OSC32_OUT_4") (pintype "bidirectional"))
    )
    (net (code "86") (name "TXD") (class "Default")
      (node (ref "U1") (pin "26") (pinfunction "TXD_26") (pintype "output"))
      (node (ref "U2") (pin "3") (pinfunction "IN_B_3") (pintype "input"))
    )
    (net (code "87") (name "USART_RX") (class "Default")
      (node (ref "R15") (pin "1") (pinfunction "1_1") (pintype "passive"))
      (node (ref "R6") (pin "2") (pinfunction "2_2") (pintype "passive"))
      (node (ref "U6") (pin "31") (pinfunction "PA10_31") (pintype "bidirectional"))
    )
    (net (code "88") (name "USART_TX") (class "Default")
      (node (ref "R16") (pin "1") (pinfunction "1_1") (pintype "passive"))
      (node (ref "R5") (pin "2") (pinfunction "2_2") (pintype "passive"))
      (node (ref "U6") (pin "30") (pinfunction "PA9_30") (pintype "bidirectional"))
    )
    (net (code "89") (name "USB_DET") (class "Default")
      (node (ref "R2") (pin "1") (pinfunction "1_1") (pintype "passive"))
      (node (ref "R3") (pin "1") (pinfunction "1_1") (pintype "passive"))
      (node (ref "U1") (pin "8") (pinfunction "VBUS_8") (pintype "input"))
    )
    (net (code "90") (name "USB_RXD") (class "Default")
      (node (ref "R5") (pin "1") (pinfunction "1_1") (pintype "passive"))
      (node (ref "U2") (pin "7") (pinfunction "INA_A_7") (pintype "input"))
    )
    (net (code "91") (name "USB_TXD") (class "Default")
      (node (ref "R6") (pin "1") (pinfunction "1_1") (pintype "passive"))
      (node (ref "U2") (pin "6") (pinfunction "OUT_B_6") (pintype "output"))
    )
    (net (code "92") (name "VBAT") (class "Default")
      (node (ref "U6") (pin "1") (pinfunction "VBAT_1") (pintype "power_in"))
    )
    (net (code "93") (name "VDD_BRIDGE") (class "Default")
      (node (ref "C11") (pin "P$1") (pinfunction "1_P$1") (pintype "passive"))
      (node (ref "C8") (pin "P$1") (pinfunction "1_P$1") (pintype "passive"))
      (node (ref "R4") (pin "1") (pinfunction "1_1") (pintype "passive"))
      (node (ref "U1") (pin "6") (pinfunction "VDD_6") (pintype "power_in"))
    )
    (net (code "94") (name "VREF_SDADC") (class "Default")
      (node (ref "C34") (pin "P$1") (pinfunction "1_P$1") (pintype "passive"))
      (node (ref "C35") (pin "P$1") (pinfunction "1_P$1") (pintype "passive"))
      (node (ref "SJ3") (pin "2") (pinfunction "2_2") (pintype "passive"))
      (node (ref "U6") (pin "25") (pinfunction "VREFSD+_25") (pintype "input"))
    )
    (net (code "95") (name "VUSB") (class "Default")
      (node (ref "C1") (pin "P$1") (pinfunction "1_P$1") (pintype "passive"))
      (node (ref "C12") (pin "P$1") (pinfunction "1_P$1") (pintype "passive"))
      (node (ref "C2") (pin "P$1") (pinfunction "1_P$1") (pintype "passive"))
      (node (ref "C4") (pin "P$1") (pinfunction "1_P$1") (pintype "passive"))
      (node (ref "C5") (pin "P$1") (pinfunction "1_P$1") (pintype "passive"))
      (node (ref "D1") (pin "A") (pinfunction "P$1_A") (pintype "bidirectional"))
      (node (ref "J1") (pin "1") (pinfunction "VCC_1") (pintype "power_in"))
      (node (ref "PS1") (pin "+VIN") (pinfunction "+VIN_+VIN") (pintype "passive"))
      (node (ref "PS2") (pin "+VIN") (pinfunction "+VIN_+VIN") (pintype "passive"))
      (node (ref "R2") (pin "2") (pinfunction "2_2") (pintype "passive"))
      (node (ref "U1") (pin "7") (pinfunction "REGIN_7") (pintype "power_in"))
      (node (ref "U2") (pin "1") (pinfunction "VCC1_1") (pintype "power_in"))
    )
    (net (code "96") (name "unconnected-(J3-Pad01)") (class "Default")
      (node (ref "J3") (pin "01") (pinfunction "01_01") (pintype "passive"))
    )
    (net (code "97") (name "unconnected-(J3-Pad02)") (class "Default")
      (node (ref "J3") (pin "02") (pinfunction "02_02") (pintype "passive"))
    )
    (net (code "98") (name "unconnected-(J3-Pad11)") (class "Default")
      (node (ref "J3") (pin "11") (pinfunction "11_11") (pintype "passive"))
    )
    (net (code "99") (name "unconnected-(U1-CHR0-Pad15)") (class "Default")
      (node (ref "U1") (pin "15") (pinfunction "CHR0_15") (pintype "output"))
    )
    (net (code "100") (name "unconnected-(U1-CHR1-Pad14)") (class "Default")
      (node (ref "U1") (pin "14") (pinfunction "CHR1_14") (pintype "output"))
    )
    (net (code "101") (name "unconnected-(U1-CHREN-Pad13)") (class "Default")
      (node (ref "U1") (pin "13") (pinfunction "CHREN_13") (pintype "output"))
    )
    (net (code "102") (name "unconnected-(U1-CTS-Pad23)") (class "Default")
      (node (ref "U1") (pin "23") (pinfunction "CTS_23") (pintype "input"))
    )
    (net (code "103") (name "unconnected-(U1-DCD-Pad1)") (class "Default")
      (node (ref "U1") (pin "1") (pinfunction "DCD_1") (pintype "input"))
    )
    (net (code "104") (name "unconnected-(U1-DSR-Pad27)") (class "Default")
      (node (ref "U1") (pin "27") (pinfunction "DSR_27") (pintype "input"))
    )
    (net (code "105") (name "unconnected-(U1-DTR-Pad28)") (class "Default")
      (node (ref "U1") (pin "28") (pinfunction "DTR_28") (pintype "output"))
    )
    (net (code "106") (name "unconnected-(U1-GPIO0{slash}TXT-Pad19)") (class "Default")
      (node (ref "U1") (pin "19") (pinfunction "GPIO0/TXT_19") (pintype "bidirectional"))
    )
    (net (code "107") (name "unconnected-(U1-GPIO1{slash}RXT-Pad18)") (class "Default")
      (node (ref "U1") (pin "18") (pinfunction "GPIO1/RXT_18") (pintype "bidirectional"))
    )
    (net (code "108") (name "unconnected-(U1-GPIO2{slash}RS485-Pad17)") (class "Default")
      (node (ref "U1") (pin "17") (pinfunction "GPIO2/RS485_17") (pintype "bidirectional"))
    )
    (net (code "109") (name "unconnected-(U1-GPIO3{slash}WAKEUP-Pad16)") (class "Default")
      (node (ref "U1") (pin "16") (pinfunction "GPIO3/WAKEUP_16") (pintype "bidirectional"))
    )
    (net (code "110") (name "unconnected-(U1-GPIO4-Pad22)") (class "Default")
      (node (ref "U1") (pin "22") (pinfunction "GPIO4_22") (pintype "bidirectional"))
    )
    (net (code "111") (name "unconnected-(U1-GPIO5-Pad21)") (class "Default")
      (node (ref "U1") (pin "21") (pinfunction "GPIO5_21") (pintype "bidirectional"))
    )
    (net (code "112") (name "unconnected-(U1-GPIO6-Pad20)") (class "Default")
      (node (ref "U1") (pin "20") (pinfunction "GPIO6_20") (pintype "bidirectional"))
    )
    (net (code "113") (name "unconnected-(U1-RI-Pad2)") (class "Default")
      (node (ref "U1") (pin "2") (pinfunction "RI_2") (pintype "bidirectional"))
    )
    (net (code "114") (name "unconnected-(U1-RTS-Pad24)") (class "Default")
      (node (ref "U1") (pin "24") (pinfunction "RTS_24") (pintype "output"))
    )
    (net (code "115") (name "unconnected-(U1-SUSPEND-Pad12)") (class "Default")
      (node (ref "U1") (pin "12") (pinfunction "SUSPEND_12") (pintype "output"))
    )
    (net (code "116") (name "unconnected-(U1-~{SUSPEND}-Pad11)") (class "Default")
      (node (ref "U1") (pin "11") (pinfunction "~{SUSPEND}_11") (pintype "output"))
    )
    (net (code "117") (name "unconnected-(U3-N{slash}C-Pad4)") (class "Default")
      (node (ref "U3") (pin "4") (pinfunction "N/C_4") (pintype "no_connect"))
    )
    (net (code "118") (name "unconnected-(U4-N{slash}C-Pad4)") (class "Default")
      (node (ref "U4") (pin "4") (pinfunction "N/C_4") (pintype "no_connect"))
    )
    (net (code "119") (name "unconnected-(U6-PA0-Pad10)") (class "Default")
      (node (ref "U6") (pin "10") (pinfunction "PA0_10") (pintype "bidirectional"))
    )
    (net (code "120") (name "unconnected-(U6-PA1-Pad11)") (class "Default")
      (node (ref "U6") (pin "11") (pinfunction "PA1_11") (pintype "bidirectional"))
    )
    (net (code "121") (name "unconnected-(U6-PA2-Pad12)") (class "Default")
      (node (ref "U6") (pin "12") (pinfunction "PA2_12") (pintype "bidirectional"))
    )
    (net (code "122") (name "unconnected-(U6-PA6-Pad16)") (class "Default")
      (node (ref "U6") (pin "16") (pinfunction "PA6_16") (pintype "bidirectional"))
    )
    (net (code "123") (name "unconnected-(U6-PA8-Pad29)") (class "Default")
      (node (ref "U6") (pin "29") (pinfunction "PA8_29") (pintype "bidirectional"))
    )
    (net (code "124") (name "unconnected-(U6-PA11-Pad32)") (class "Default")
      (node (ref "U6") (pin "32") (pinfunction "PA11_32") (pintype "bidirectional"))
    )
    (net (code "125") (name "unconnected-(U6-PA12-Pad33)") (class "Default")
      (node (ref "U6") (pin "33") (pinfunction "PA12_33") (pintype "bidirectional"))
    )
    (net (code "126") (name "unconnected-(U6-PB4-Pad40)") (class "Default")
      (node (ref "U6") (pin "40") (pinfunction "PB4_40") (pintype "bidirectional"))
    )
    (net (code "127") (name "unconnected-(U6-PB5-Pad41)") (class "Default")
      (node (ref "U6") (pin "41") (pinfunction "PB5_41") (pintype "bidirectional"))
    )
    (net (code "128") (name "unconnected-(U6-PD8-Pad28)") (class "Default")
      (node (ref "U6") (pin "28") (pinfunction "PD8_28") (pintype "bidirectional"))
    )
    (net (code "129") (name "unconnected-(U6-PF6-Pad35)") (class "Default")
      (node (ref "U6") (pin "35") (pinfunction "PF6_35") (pintype "bidirectional"))
    )
    (net (code "130") (name "unconnected-(U6-PF7-Pad36)") (class "Default")
      (node (ref "U6") (pin "36") (pinfunction "PF7_36") (pintype "bidirectional"))
    )
    (net (code "131") (name "unconnected-(U8A-B-Pad7)") (class "Default")
      (node (ref "U8") (pin "7") (pinfunction "B_7") (pintype "passive"))
    )
    (net (code "132") (name "unconnected-(U8A-E-Pad8)") (class "Default")
      (node (ref "U8") (pin "8") (pinfunction "E_8") (pintype "passive"))
    )
    (net (code "133") (name "unconnected-(U8B-+-Pad14)") (class "Default")
      (node (ref "U8") (pin "14") (pinfunction "+_14") (pintype "bidirectional"))
    )
    (net (code "134") (name "unconnected-(U8B---Pad13)") (class "Default")
      (node (ref "U8") (pin "13") (pinfunction "-_13") (pintype "bidirectional"))
    )
    (net (code "135") (name "unconnected-(U8B-B-Pad10)") (class "Default")
      (node (ref "U8") (pin "10") (pinfunction "B_10") (pintype "passive"))
    )
    (net (code "136") (name "unconnected-(U8B-D_BIAS-Pad15)") (class "Default")
      (node (ref "U8") (pin "15") (pinfunction "D_BIAS_15") (pintype "bidirectional"))
    )
    (net (code "137") (name "unconnected-(U8B-E-Pad9)") (class "Default")
      (node (ref "U8") (pin "9") (pinfunction "E_9") (pintype "passive"))
    )
    (net (code "138") (name "unconnected-(U8B-OUT-Pad12)") (class "Default")
      (node (ref "U8") (pin "12") (pinfunction "OUT_12") (pintype "bidirectional"))
    )
  )
)
